# GEO-HEX-1_0_0.net
KiCad netlist of a schematic drawn in EAGLE
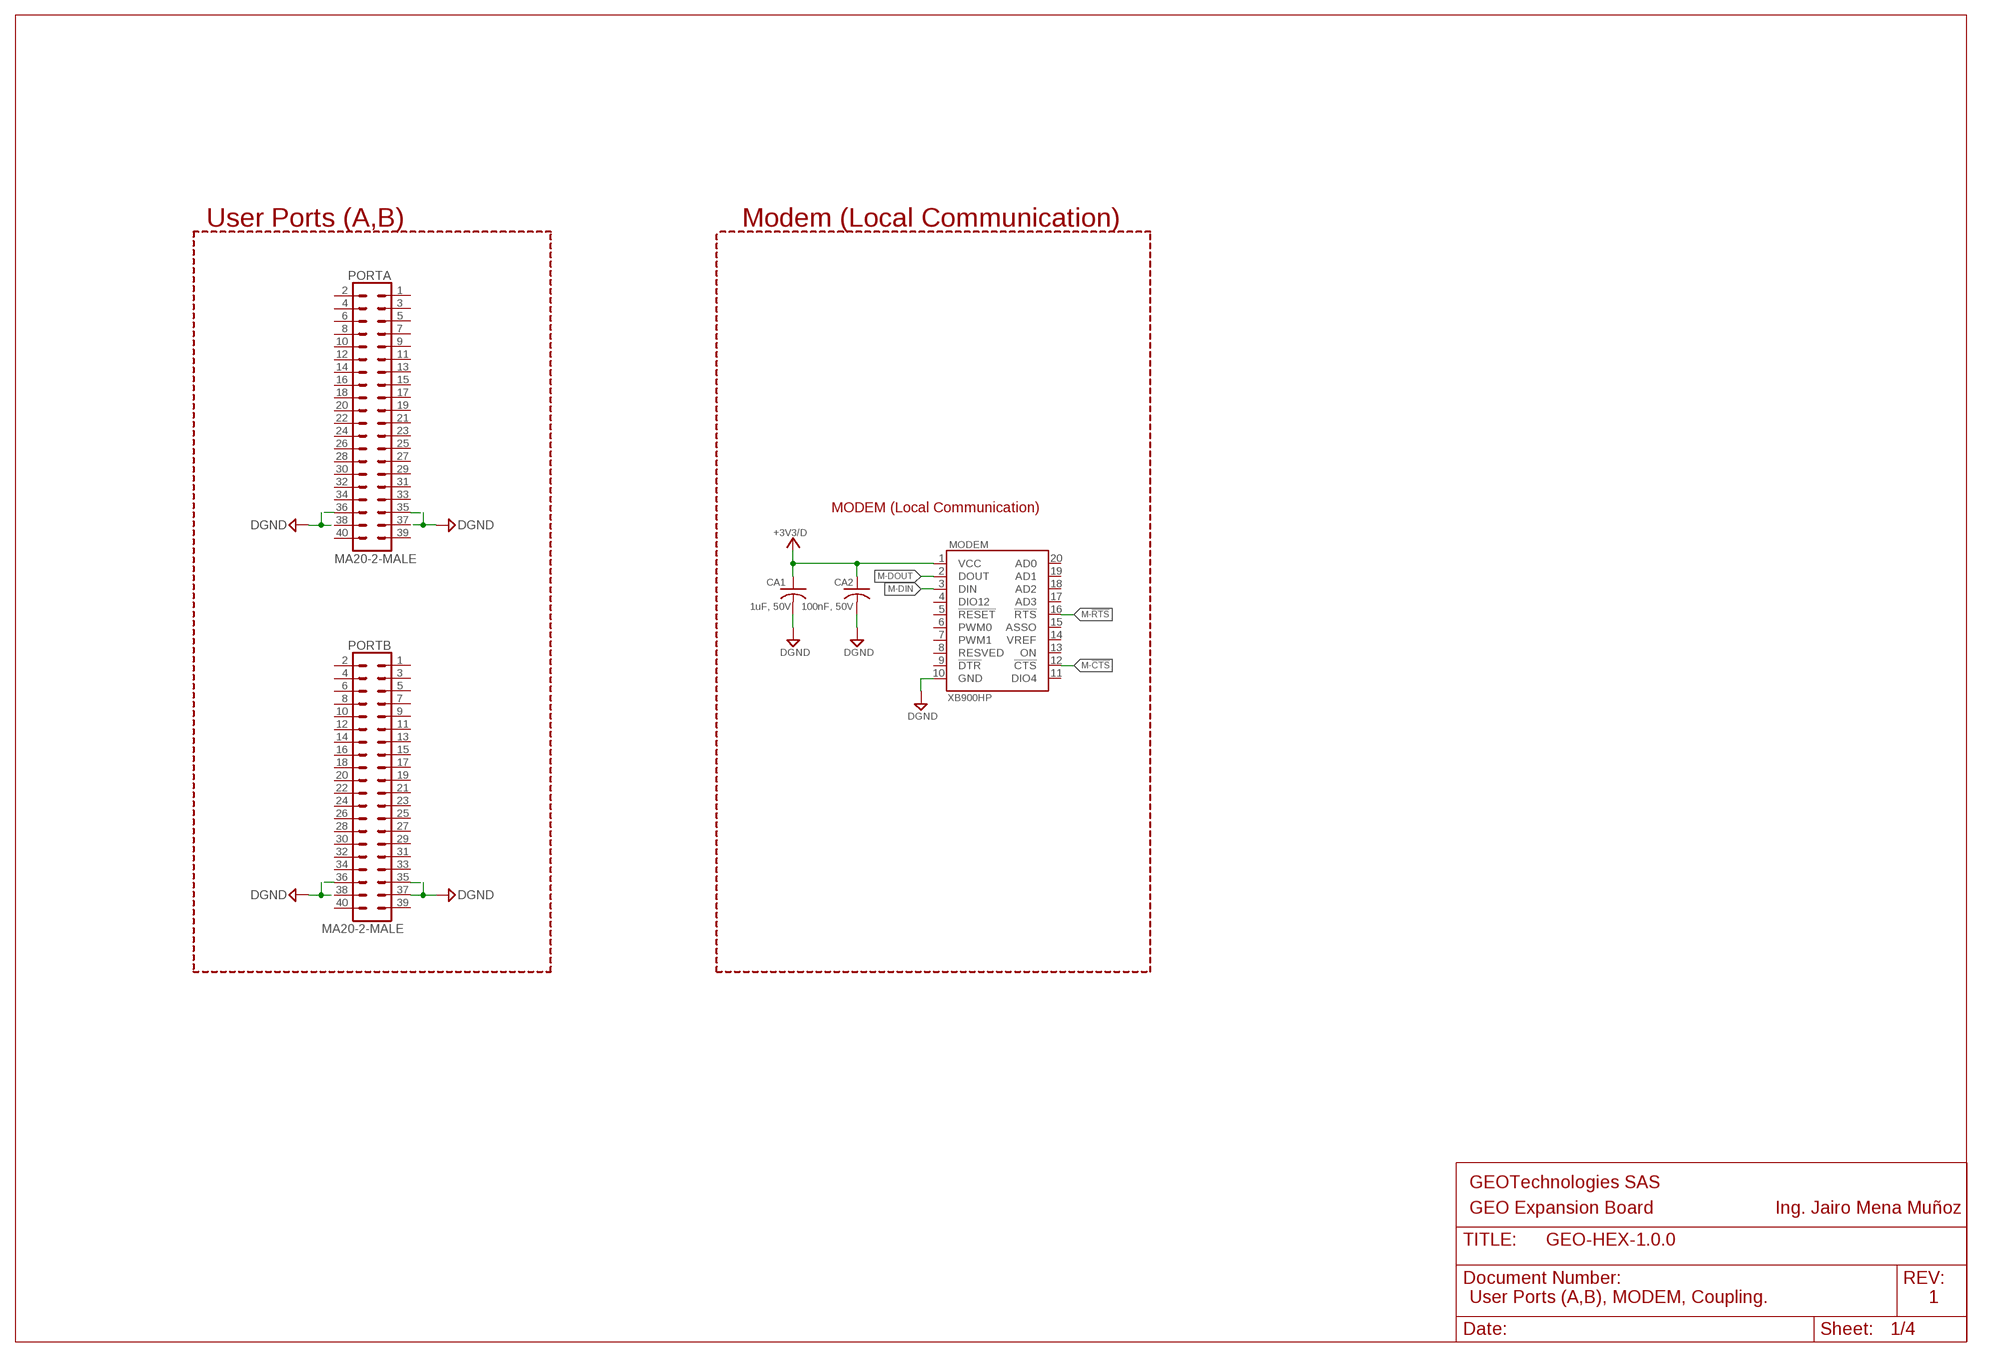
[diagram p0: schematic, sheet 1]
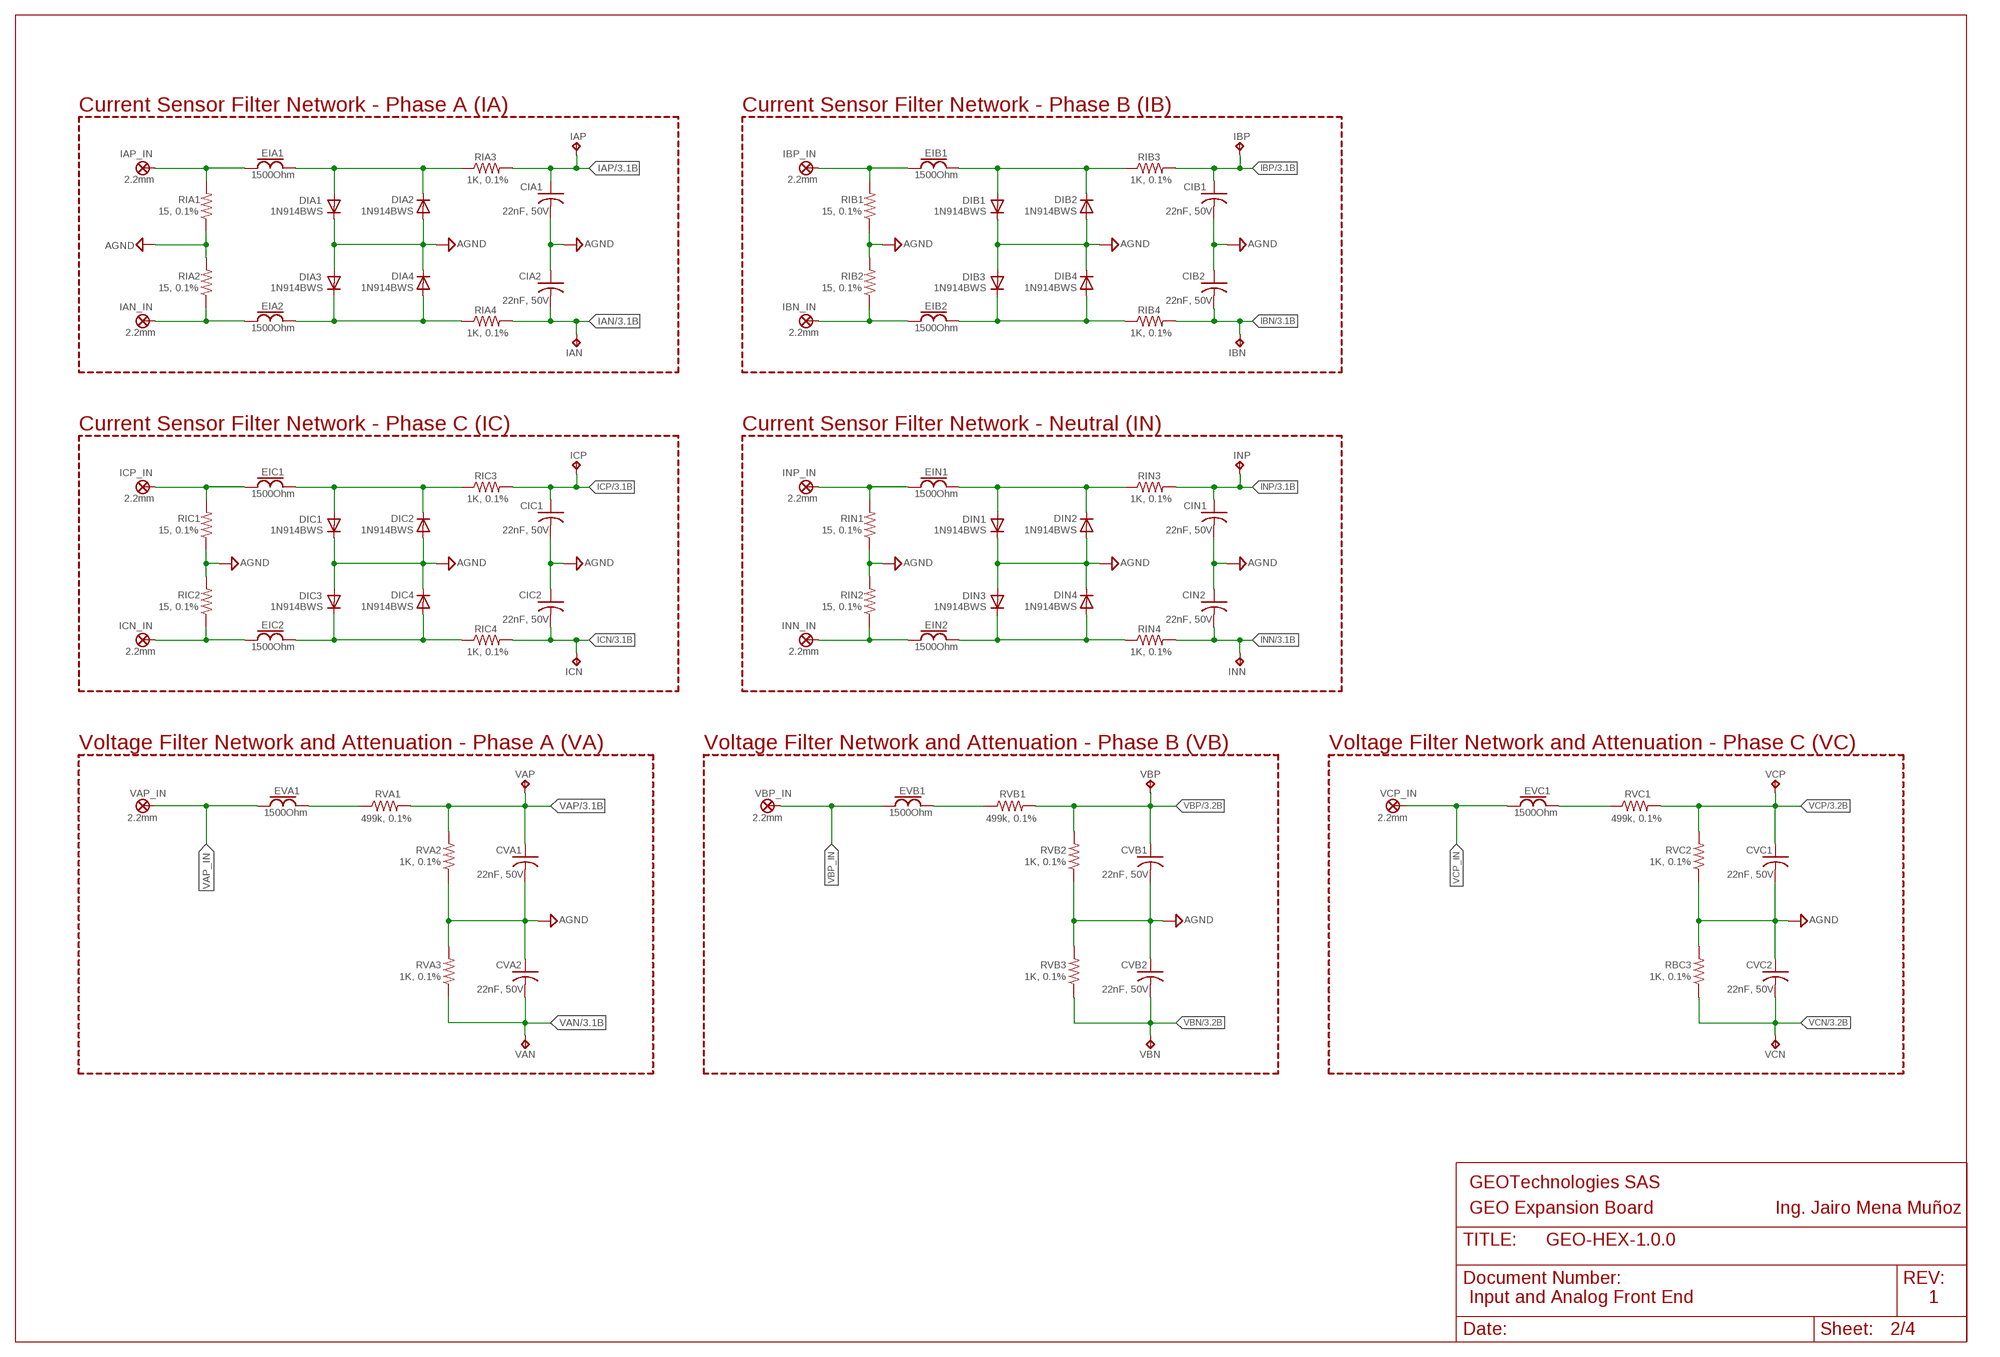
[diagram p1: schematic, sheet 2]
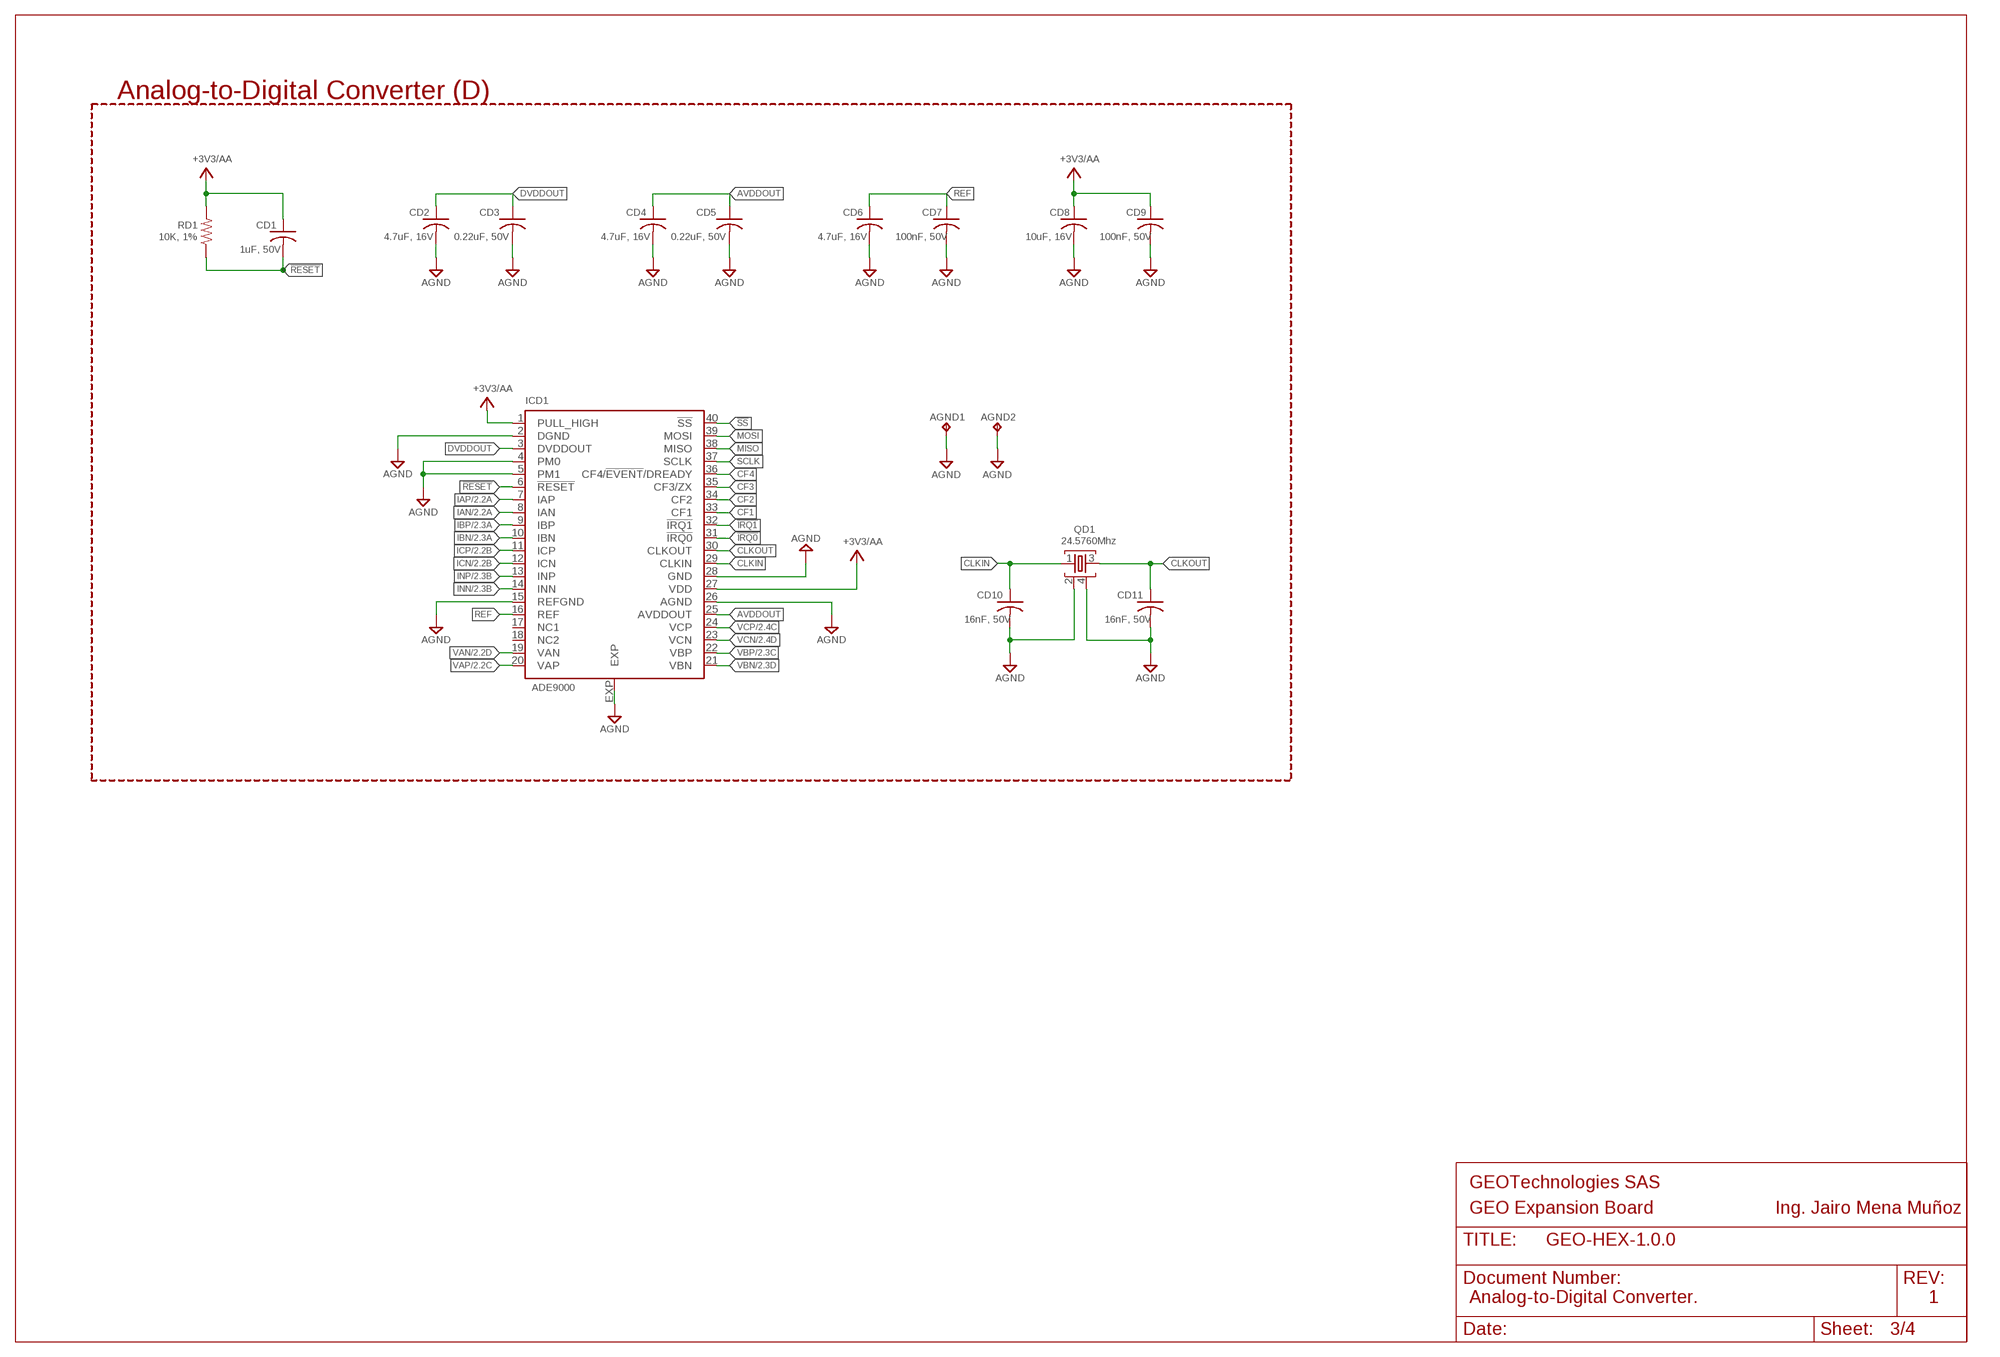
[diagram p2: schematic, sheet 3]
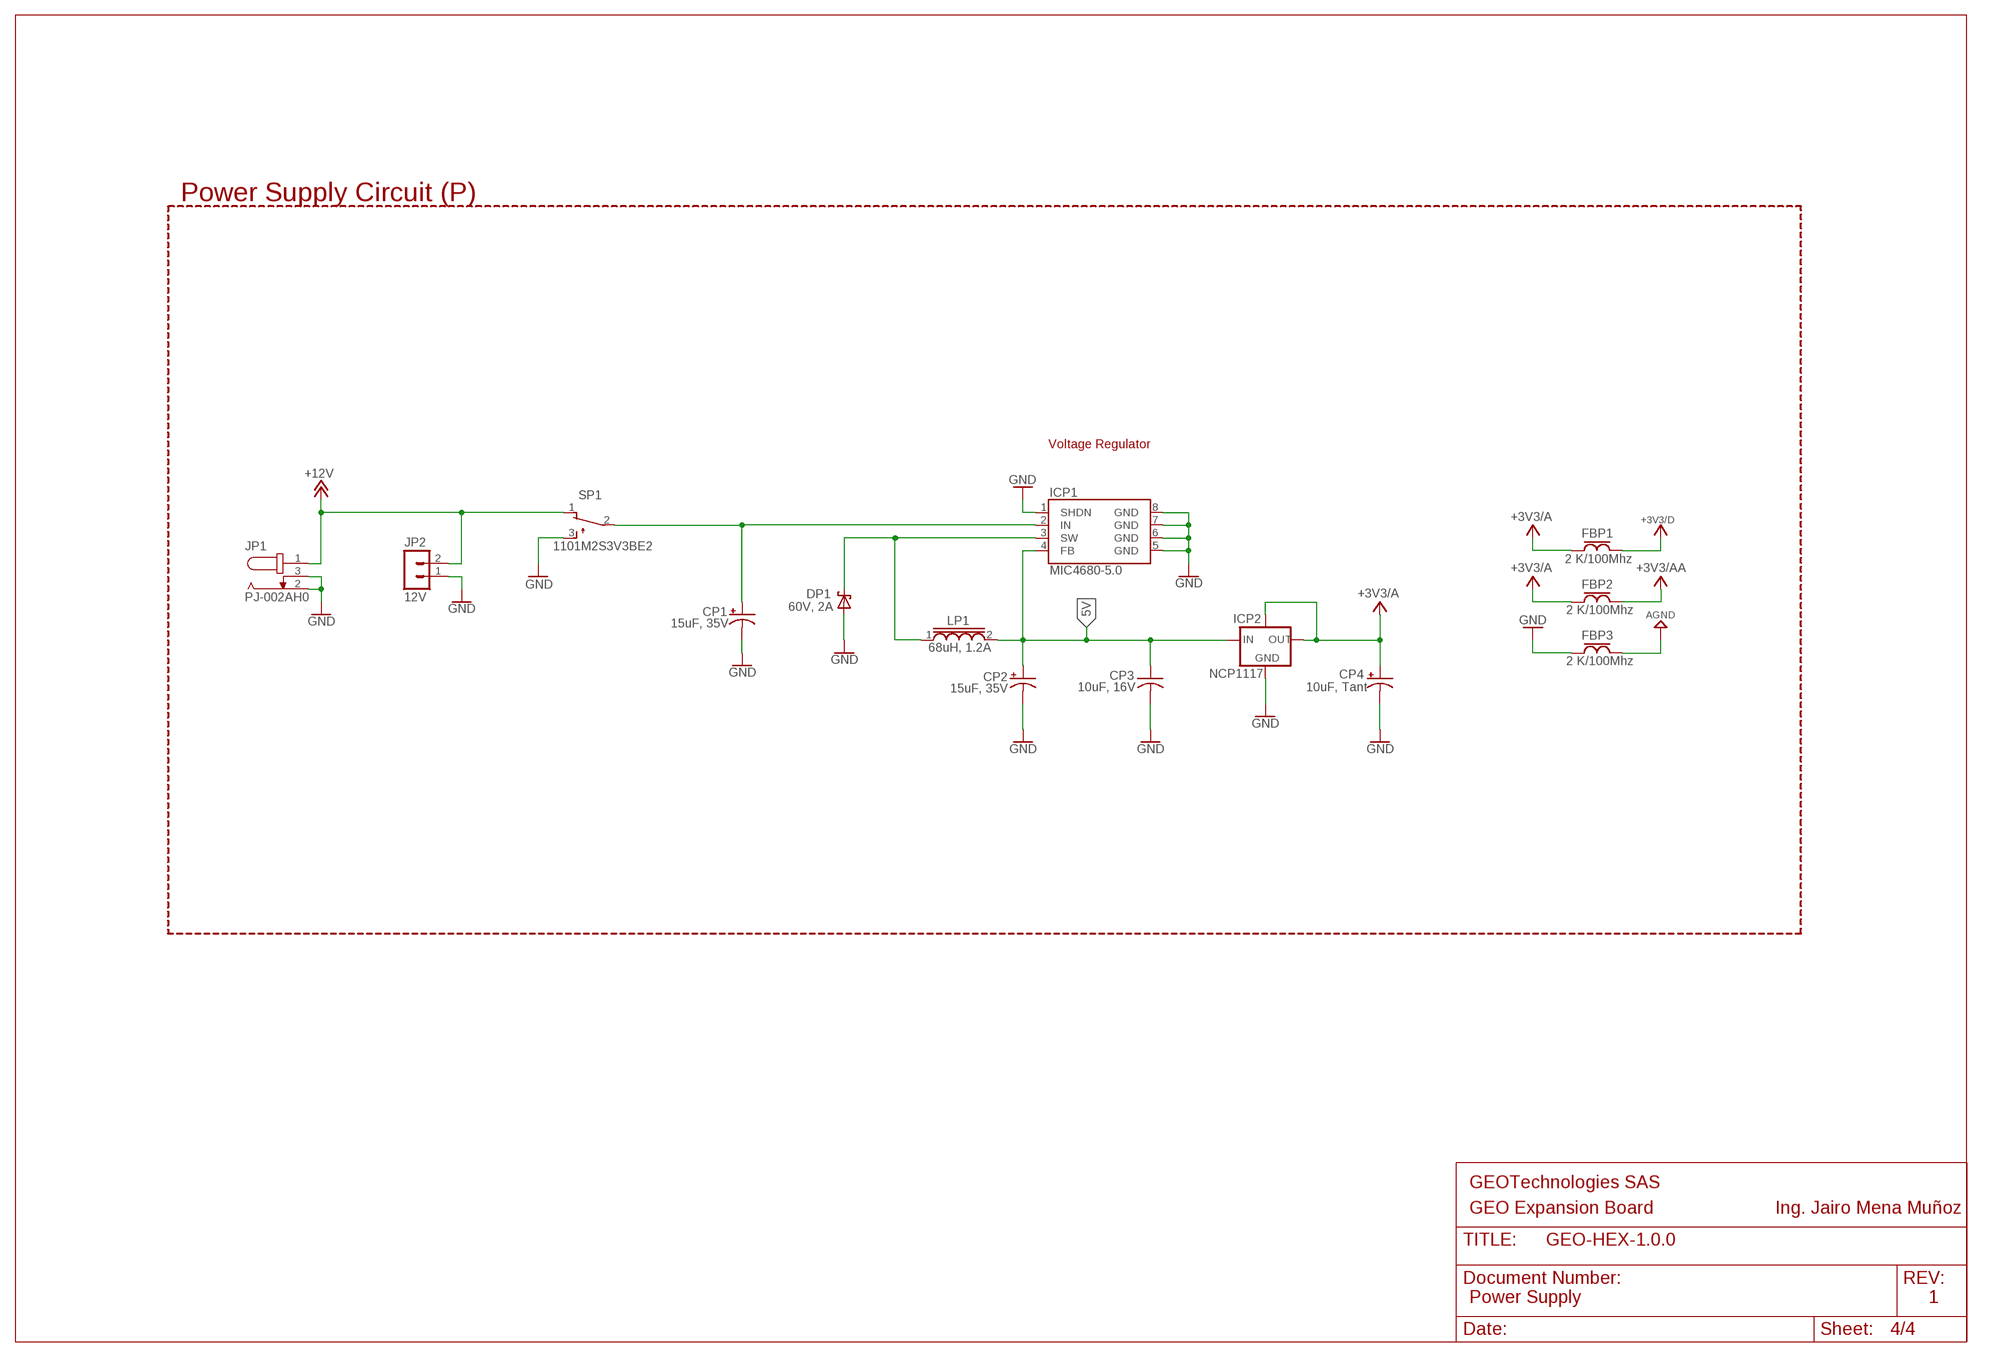
[diagram p3: schematic, sheet 4]

(export (version "E")
  (design (tool "Eeschema 10.0.6"))
  (components
    (comp (ref "CIA1")
      (value "22nF, 50V")
      (footprint "eagle-import:C0805")
      (libsource (lib "eagle-import") (part "C-US22NF-0805"))
    )
    (comp (ref "CIA2")
      (value "22nF, 50V")
      (footprint "eagle-import:C0805")
      (libsource (lib "eagle-import") (part "C-US22NF-0805"))
    )
    (comp (ref "CIB1")
      (value "22nF, 50V")
      (footprint "eagle-import:C0805")
      (libsource (lib "eagle-import") (part "C-US22NF-0805"))
    )
    (comp (ref "CIB2")
      (value "22nF, 50V")
      (footprint "eagle-import:C0805")
      (libsource (lib "eagle-import") (part "C-US22NF-0805"))
    )
    (comp (ref "CIC1")
      (value "22nF, 50V")
      (footprint "eagle-import:C0805")
      (libsource (lib "eagle-import") (part "C-US22NF-0805"))
    )
    (comp (ref "CIC2")
      (value "22nF, 50V")
      (footprint "eagle-import:C0805")
      (libsource (lib "eagle-import") (part "C-US22NF-0805"))
    )
    (comp (ref "CIN1")
      (value "22nF, 50V")
      (footprint "eagle-import:C0805")
      (libsource (lib "eagle-import") (part "C-US22NF-0805"))
    )
    (comp (ref "CIN2")
      (value "22nF, 50V")
      (footprint "eagle-import:C0805")
      (libsource (lib "eagle-import") (part "C-US22NF-0805"))
    )
    (comp (ref "CVA1")
      (value "22nF, 50V")
      (footprint "eagle-import:C0805")
      (libsource (lib "eagle-import") (part "C-US22NF-0805"))
    )
    (comp (ref "CVA2")
      (value "22nF, 50V")
      (footprint "eagle-import:C0805")
      (libsource (lib "eagle-import") (part "C-US22NF-0805"))
    )
    (comp (ref "CVB1")
      (value "22nF, 50V")
      (footprint "eagle-import:C0805")
      (libsource (lib "eagle-import") (part "C-US22NF-0805"))
    )
    (comp (ref "CVB2")
      (value "22nF, 50V")
      (footprint "eagle-import:C0805")
      (libsource (lib "eagle-import") (part "C-US22NF-0805"))
    )
    (comp (ref "CVC1")
      (value "22nF, 50V")
      (footprint "eagle-import:C0805")
      (libsource (lib "eagle-import") (part "C-US22NF-0805"))
    )
    (comp (ref "CVC2")
      (value "22nF, 50V")
      (footprint "eagle-import:C0805")
      (libsource (lib "eagle-import") (part "C-US22NF-0805"))
    )
    (comp (ref "DIA1")
      (value "1N914BWS")
      (footprint "eagle-import:SOD-323FL")
      (libsource (lib "eagle-import") (part "D1N914BWS"))
    )
    (comp (ref "DIA2")
      (value "1N914BWS")
      (footprint "eagle-import:SOD-323FL")
      (libsource (lib "eagle-import") (part "D1N914BWS"))
    )
    (comp (ref "DIA3")
      (value "1N914BWS")
      (footprint "eagle-import:SOD-323FL")
      (libsource (lib "eagle-import") (part "D1N914BWS"))
    )
    (comp (ref "DIA4")
      (value "1N914BWS")
      (footprint "eagle-import:SOD-323FL")
      (libsource (lib "eagle-import") (part "D1N914BWS"))
    )
    (comp (ref "DIB1")
      (value "1N914BWS")
      (footprint "eagle-import:SOD-323FL")
      (libsource (lib "eagle-import") (part "D1N914BWS"))
    )
    (comp (ref "DIB2")
      (value "1N914BWS")
      (footprint "eagle-import:SOD-323FL")
      (libsource (lib "eagle-import") (part "D1N914BWS"))
    )
    (comp (ref "DIB3")
      (value "1N914BWS")
      (footprint "eagle-import:SOD-323FL")
      (libsource (lib "eagle-import") (part "D1N914BWS"))
    )
    (comp (ref "DIB4")
      (value "1N914BWS")
      (footprint "eagle-import:SOD-323FL")
      (libsource (lib "eagle-import") (part "D1N914BWS"))
    )
    (comp (ref "DIC1")
      (value "1N914BWS")
      (footprint "eagle-import:SOD-323FL")
      (libsource (lib "eagle-import") (part "D1N914BWS"))
    )
    (comp (ref "DIC2")
      (value "1N914BWS")
      (footprint "eagle-import:SOD-323FL")
      (libsource (lib "eagle-import") (part "D1N914BWS"))
    )
    (comp (ref "DIC3")
      (value "1N914BWS")
      (footprint "eagle-import:SOD-323FL")
      (libsource (lib "eagle-import") (part "D1N914BWS"))
    )
    (comp (ref "DIC4")
      (value "1N914BWS")
      (footprint "eagle-import:SOD-323FL")
      (libsource (lib "eagle-import") (part "D1N914BWS"))
    )
    (comp (ref "DIN1")
      (value "1N914BWS")
      (footprint "eagle-import:SOD-323FL")
      (libsource (lib "eagle-import") (part "D1N914BWS"))
    )
    (comp (ref "DIN2")
      (value "1N914BWS")
      (footprint "eagle-import:SOD-323FL")
      (libsource (lib "eagle-import") (part "D1N914BWS"))
    )
    (comp (ref "DIN3")
      (value "1N914BWS")
      (footprint "eagle-import:SOD-323FL")
      (libsource (lib "eagle-import") (part "D1N914BWS"))
    )
    (comp (ref "DIN4")
      (value "1N914BWS")
      (footprint "eagle-import:SOD-323FL")
      (libsource (lib "eagle-import") (part "D1N914BWS"))
    )
    (comp (ref "EIA1")
      (value "1500Ohm")
      (footprint "eagle-import:L0805")
      (libsource (lib "eagle-import") (part "FBL0805"))
    )
    (comp (ref "EIA2")
      (value "1500Ohm")
      (footprint "eagle-import:L0805")
      (libsource (lib "eagle-import") (part "FBL0805"))
    )
    (comp (ref "EIB1")
      (value "1500Ohm")
      (footprint "eagle-import:L0805")
      (libsource (lib "eagle-import") (part "FBL0805"))
    )
    (comp (ref "EIB2")
      (value "1500Ohm")
      (footprint "eagle-import:L0805")
      (libsource (lib "eagle-import") (part "FBL0805"))
    )
    (comp (ref "EIC1")
      (value "1500Ohm")
      (footprint "eagle-import:L0805")
      (libsource (lib "eagle-import") (part "FBL0805"))
    )
    (comp (ref "EIC2")
      (value "1500Ohm")
      (footprint "eagle-import:L0805")
      (libsource (lib "eagle-import") (part "FBL0805"))
    )
    (comp (ref "EIN1")
      (value "1500Ohm")
      (footprint "eagle-import:L0805")
      (libsource (lib "eagle-import") (part "FBL0805"))
    )
    (comp (ref "EIN2")
      (value "1500Ohm")
      (footprint "eagle-import:L0805")
      (libsource (lib "eagle-import") (part "FBL0805"))
    )
    (comp (ref "EVA1")
      (value "1500Ohm")
      (footprint "eagle-import:L0805")
      (libsource (lib "eagle-import") (part "FBL0805"))
    )
    (comp (ref "EVB1")
      (value "1500Ohm")
      (footprint "eagle-import:L0805")
      (libsource (lib "eagle-import") (part "FBL0805"))
    )
    (comp (ref "EVC1")
      (value "1500Ohm")
      (footprint "eagle-import:L0805")
      (libsource (lib "eagle-import") (part "FBL0805"))
    )
    (comp (ref "IAN")
      (value "TPPAD1-13")
      (footprint "eagle-import:P1-10")
      (libsource (lib "eagle-import") (part "TPPAD1-13"))
    )
    (comp (ref "IAN_IN")
      (value "2.2mm")
      (footprint "eagle-import:TURRET")
      (libsource (lib "eagle-import") (part "TURRET"))
    )
    (comp (ref "IAP")
      (value "TPPAD1-13")
      (footprint "eagle-import:P1-10")
      (libsource (lib "eagle-import") (part "TPPAD1-13"))
    )
    (comp (ref "IAP_IN")
      (value "2.2mm")
      (footprint "eagle-import:TURRET")
      (libsource (lib "eagle-import") (part "TURRET"))
    )
    (comp (ref "IBN")
      (value "TPPAD1-13")
      (footprint "eagle-import:P1-10")
      (libsource (lib "eagle-import") (part "TPPAD1-13"))
    )
    (comp (ref "IBN_IN")
      (value "2.2mm")
      (footprint "eagle-import:TURRET")
      (libsource (lib "eagle-import") (part "TURRET"))
    )
    (comp (ref "IBP")
      (value "TPPAD1-13")
      (footprint "eagle-import:P1-10")
      (libsource (lib "eagle-import") (part "TPPAD1-13"))
    )
    (comp (ref "IBP_IN")
      (value "2.2mm")
      (footprint "eagle-import:TURRET")
      (libsource (lib "eagle-import") (part "TURRET"))
    )
    (comp (ref "ICN")
      (value "TPPAD1-13")
      (footprint "eagle-import:P1-10")
      (libsource (lib "eagle-import") (part "TPPAD1-13"))
    )
    (comp (ref "ICN_IN")
      (value "2.2mm")
      (footprint "eagle-import:TURRET")
      (libsource (lib "eagle-import") (part "TURRET"))
    )
    (comp (ref "ICP")
      (value "TPPAD1-13")
      (footprint "eagle-import:P1-10")
      (libsource (lib "eagle-import") (part "TPPAD1-13"))
    )
    (comp (ref "ICP_IN")
      (value "2.2mm")
      (footprint "eagle-import:TURRET")
      (libsource (lib "eagle-import") (part "TURRET"))
    )
    (comp (ref "INN")
      (value "TPPAD1-13")
      (footprint "eagle-import:P1-10")
      (libsource (lib "eagle-import") (part "TPPAD1-13"))
    )
    (comp (ref "INN_IN")
      (value "2.2mm")
      (footprint "eagle-import:TURRET")
      (libsource (lib "eagle-import") (part "TURRET"))
    )
    (comp (ref "INP")
      (value "TPPAD1-13")
      (footprint "eagle-import:P1-10")
      (libsource (lib "eagle-import") (part "TPPAD1-13"))
    )
    (comp (ref "INP_IN")
      (value "2.2mm")
      (footprint "eagle-import:TURRET")
      (libsource (lib "eagle-import") (part "TURRET"))
    )
    (comp (ref "RBC3")
      (value "1K, 0.1%")
      (footprint "eagle-import:R0805")
      (libsource (lib "eagle-import") (part "R-US1KR0805"))
    )
    (comp (ref "RIA1")
      (value "15, 0.1%")
      (footprint "eagle-import:R0805")
      (libsource (lib "eagle-import") (part "R-US15R0805"))
    )
    (comp (ref "RIA2")
      (value "15, 0.1%")
      (footprint "eagle-import:R0805")
      (libsource (lib "eagle-import") (part "R-US15R0805"))
    )
    (comp (ref "RIA3")
      (value "1K, 0.1%")
      (footprint "eagle-import:R0805")
      (libsource (lib "eagle-import") (part "R-US1KR0805"))
    )
    (comp (ref "RIA4")
      (value "1K, 0.1%")
      (footprint "eagle-import:R0805")
      (libsource (lib "eagle-import") (part "R-US1KR0805"))
    )
    (comp (ref "RIB1")
      (value "15, 0.1%")
      (footprint "eagle-import:R0805")
      (libsource (lib "eagle-import") (part "R-US15R0805"))
    )
    (comp (ref "RIB2")
      (value "15, 0.1%")
      (footprint "eagle-import:R0805")
      (libsource (lib "eagle-import") (part "R-US15R0805"))
    )
    (comp (ref "RIB3")
      (value "1K, 0.1%")
      (footprint "eagle-import:R0805")
      (libsource (lib "eagle-import") (part "R-US1KR0805"))
    )
    (comp (ref "RIB4")
      (value "1K, 0.1%")
      (footprint "eagle-import:R0805")
      (libsource (lib "eagle-import") (part "R-US1KR0805"))
    )
    (comp (ref "RIC1")
      (value "15, 0.1%")
      (footprint "eagle-import:R0805")
      (libsource (lib "eagle-import") (part "R-US15R0805"))
    )
    (comp (ref "RIC2")
      (value "15, 0.1%")
      (footprint "eagle-import:R0805")
      (libsource (lib "eagle-import") (part "R-US15R0805"))
    )
    (comp (ref "RIC3")
      (value "1K, 0.1%")
      (footprint "eagle-import:R0805")
      (libsource (lib "eagle-import") (part "R-US1KR0805"))
    )
    (comp (ref "RIC4")
      (value "1K, 0.1%")
      (footprint "eagle-import:R0805")
      (libsource (lib "eagle-import") (part "R-US1KR0805"))
    )
    (comp (ref "RIN1")
      (value "15, 0.1%")
      (footprint "eagle-import:R0805")
      (libsource (lib "eagle-import") (part "R-US15R0805"))
    )
    (comp (ref "RIN2")
      (value "15, 0.1%")
      (footprint "eagle-import:R0805")
      (libsource (lib "eagle-import") (part "R-US15R0805"))
    )
    (comp (ref "RIN3")
      (value "1K, 0.1%")
      (footprint "eagle-import:R0805")
      (libsource (lib "eagle-import") (part "R-US1KR0805"))
    )
    (comp (ref "RIN4")
      (value "1K, 0.1%")
      (footprint "eagle-import:R0805")
      (libsource (lib "eagle-import") (part "R-US1KR0805"))
    )
    (comp (ref "RVA1")
      (value "499k, 0.1%")
      (footprint "eagle-import:R1206")
      (libsource (lib "eagle-import") (part "R-US499KR1206"))
    )
    (comp (ref "RVA2")
      (value "1K, 0.1%")
      (footprint "eagle-import:R0805")
      (libsource (lib "eagle-import") (part "R-US1KR0805"))
    )
    (comp (ref "RVA3")
      (value "1K, 0.1%")
      (footprint "eagle-import:R0805")
      (libsource (lib "eagle-import") (part "R-US1KR0805"))
    )
    (comp (ref "RVB1")
      (value "499k, 0.1%")
      (footprint "eagle-import:R1206")
      (libsource (lib "eagle-import") (part "R-US499KR1206"))
    )
    (comp (ref "RVB2")
      (value "1K, 0.1%")
      (footprint "eagle-import:R0805")
      (libsource (lib "eagle-import") (part "R-US1KR0805"))
    )
    (comp (ref "RVB3")
      (value "1K, 0.1%")
      (footprint "eagle-import:R0805")
      (libsource (lib "eagle-import") (part "R-US1KR0805"))
    )
    (comp (ref "RVC1")
      (value "499k, 0.1%")
      (footprint "eagle-import:R1206")
      (libsource (lib "eagle-import") (part "R-US499KR1206"))
    )
    (comp (ref "RVC2")
      (value "1K, 0.1%")
      (footprint "eagle-import:R0805")
      (libsource (lib "eagle-import") (part "R-US1KR0805"))
    )
    (comp (ref "VAN")
      (value "TPPAD1-13")
      (footprint "eagle-import:P1-10")
      (libsource (lib "eagle-import") (part "TPPAD1-13"))
    )
    (comp (ref "VAP")
      (value "TPPAD1-13")
      (footprint "eagle-import:P1-10")
      (libsource (lib "eagle-import") (part "TPPAD1-13"))
    )
    (comp (ref "VAP_IN")
      (value "2.2mm")
      (footprint "eagle-import:TURRET")
      (libsource (lib "eagle-import") (part "TURRET"))
    )
    (comp (ref "VBN")
      (value "TPPAD1-13")
      (footprint "eagle-import:P1-10")
      (libsource (lib "eagle-import") (part "TPPAD1-13"))
    )
    (comp (ref "VBP")
      (value "TPPAD1-13")
      (footprint "eagle-import:P1-10")
      (libsource (lib "eagle-import") (part "TPPAD1-13"))
    )
    (comp (ref "VBP_IN")
      (value "2.2mm")
      (footprint "eagle-import:TURRET")
      (libsource (lib "eagle-import") (part "TURRET"))
    )
    (comp (ref "VCN")
      (value "TPPAD1-13")
      (footprint "eagle-import:P1-10")
      (libsource (lib "eagle-import") (part "TPPAD1-13"))
    )
    (comp (ref "VCP")
      (value "TPPAD1-13")
      (footprint "eagle-import:P1-10")
      (libsource (lib "eagle-import") (part "TPPAD1-13"))
    )
    (comp (ref "VCP_IN")
      (value "2.2mm")
      (footprint "eagle-import:TURRET")
      (libsource (lib "eagle-import") (part "TURRET"))
    )
    (comp (ref "CA1")
      (value "1uF, 50V")
      (footprint "eagle-import:C0805")
      (libsource (lib "eagle-import") (part "C-US1UF-0805"))
    )
    (comp (ref "CA2")
      (value "100nF, 50V")
      (footprint "eagle-import:C0805")
      (libsource (lib "eagle-import") (part "C-US100NF-0805"))
    )
    (comp (ref "MODEM")
      (value "XB900HP")
      (footprint "eagle-import:XBEEPRO")
      (libsource (lib "eagle-import") (part "XBEEPROXBP9B-DMST-002"))
    )
    (comp (ref "PORTA")
      (value "MA20-2-MALE")
      (footprint "eagle-import:MA20-2-MALE")
      (libsource (lib "eagle-import") (part "MA20-2-MALE"))
    )
    (comp (ref "PORTB")
      (value "MA20-2-MALE")
      (footprint "eagle-import:MA20-2-MALE")
      (libsource (lib "eagle-import") (part "MA20-2-MALE"))
    )
    (comp (ref "CP1")
      (value "15uF, 35V")
      (footprint "eagle-import:SMC_D")
      (libsource (lib "eagle-import") (part "C-POLSMCD"))
    )
    (comp (ref "CP2")
      (value "15uF, 35V")
      (footprint "eagle-import:SMC_D")
      (libsource (lib "eagle-import") (part "C-POLSMCD"))
    )
    (comp (ref "CP3")
      (value "10uF, 16V")
      (footprint "eagle-import:C0805")
      (libsource (lib "eagle-import") (part "C-US10UF-0805"))
    )
    (comp (ref "CP4")
      (value "10uF, Tant")
      (footprint "eagle-import:SMC_P")
      (libsource (lib "eagle-import") (part "C-POLSMCP"))
    )
    (comp (ref "DP1")
      (value "60V, 2A")
      (footprint "eagle-import:2-SMD")
      (libsource (lib "eagle-import") (part "DSB260A"))
    )
    (comp (ref "FBP1")
      (value "2 K/100Mhz")
      (footprint "eagle-import:L1210")
      (libsource (lib "eagle-import") (part "FBL1210"))
    )
    (comp (ref "FBP2")
      (value "2 K/100Mhz")
      (footprint "eagle-import:L1210")
      (libsource (lib "eagle-import") (part "FBL1210"))
    )
    (comp (ref "FBP3")
      (value "2 K/100Mhz")
      (footprint "eagle-import:L1210")
      (libsource (lib "eagle-import") (part "FBL1210"))
    )
    (comp (ref "ICP1")
      (value "MIC4680-5.0")
      (footprint "eagle-import:SO8")
      (libsource (lib "eagle-import") (part "MIC4680"))
    )
    (comp (ref "ICP2")
      (value "NCP1117")
      (footprint "eagle-import:SOT223")
      (libsource (lib "eagle-import") (part "NCP1117"))
    )
    (comp (ref "JP1")
      (value "PJ-002AH0")
      (footprint "eagle-import:JACK")
      (libsource (lib "eagle-import") (part "PJ-002AH0"))
    )
    (comp (ref "JP2")
      (value "12V")
      (footprint "eagle-import:PW2")
      (libsource (lib "eagle-import") (part "PW2"))
    )
    (comp (ref "LP1")
      (value "68uH, 1.2A")
      (footprint "eagle-import:DR7X7")
      (libsource (lib "eagle-import") (part "LVLP8040T-680M"))
    )
    (comp (ref "SP1")
      (value "1101M2S3V3BE2")
      (footprint "eagle-import:1101M2S3V3BE2")
      (libsource (lib "eagle-import") (part "1101M2S3V3BE2"))
    )
    (comp (ref "AGND1")
      (value "TPPAD1-13")
      (footprint "eagle-import:P1-10")
      (libsource (lib "eagle-import") (part "TPPAD1-13"))
    )
    (comp (ref "AGND2")
      (value "TPPAD1-13")
      (footprint "eagle-import:P1-10")
      (libsource (lib "eagle-import") (part "TPPAD1-13"))
    )
    (comp (ref "CD1")
      (value "1uF, 50V")
      (footprint "eagle-import:C0805")
      (libsource (lib "eagle-import") (part "C-US1UF-0805"))
    )
    (comp (ref "CD2")
      (value "4.7uF, 16V")
      (footprint "eagle-import:C0805")
      (libsource (lib "eagle-import") (part "C-US4.7UF-0805"))
    )
    (comp (ref "CD3")
      (value "0.22uF, 50V")
      (footprint "eagle-import:C0805")
      (libsource (lib "eagle-import") (part "C-US0.22UF-0805"))
    )
    (comp (ref "CD4")
      (value "4.7uF, 16V")
      (footprint "eagle-import:C0805")
      (libsource (lib "eagle-import") (part "C-US4.7UF-0805"))
    )
    (comp (ref "CD5")
      (value "0.22uF, 50V")
      (footprint "eagle-import:C0805")
      (libsource (lib "eagle-import") (part "C-US0.22UF-0805"))
    )
    (comp (ref "CD6")
      (value "4.7uF, 16V")
      (footprint "eagle-import:C0805")
      (libsource (lib "eagle-import") (part "C-US4.7UF-0805"))
    )
    (comp (ref "CD7")
      (value "100nF, 50V")
      (footprint "eagle-import:C0805")
      (libsource (lib "eagle-import") (part "C-US100NF-0805"))
    )
    (comp (ref "CD8")
      (value "10uF, 16V")
      (footprint "eagle-import:C0805")
      (libsource (lib "eagle-import") (part "C-US10UF-0805"))
    )
    (comp (ref "CD9")
      (value "100nF, 50V")
      (footprint "eagle-import:C0805")
      (libsource (lib "eagle-import") (part "C-US100NF-0805"))
    )
    (comp (ref "CD10")
      (value "16nF, 50V")
      (footprint "eagle-import:C0805")
      (libsource (lib "eagle-import") (part "C-US16PF-0805"))
    )
    (comp (ref "CD11")
      (value "16nF, 50V")
      (footprint "eagle-import:C0805")
      (libsource (lib "eagle-import") (part "C-US16PF-0805"))
    )
    (comp (ref "ICD1")
      (value "ADE9000")
      (footprint "eagle-import:LFCSP40")
      (libsource (lib "eagle-import") (part "ADE9000"))
    )
    (comp (ref "QD1")
      (value "24.5760Mhz")
      (footprint "eagle-import:4-SMD")
      (libsource (lib "eagle-import") (part "Q-SHIELD"))
    )
    (comp (ref "RD1")
      (value "10K, 1%")
      (footprint "eagle-import:R0805")
      (libsource (lib "eagle-import") (part "R-US10KR0805"))
    )
  )
  (nets
    (net (code "1") (name "+3V3{slash}A") (class "Default")
      (node (ref "CP4") (pin "+") (pinfunction "+_+") (pintype "passive"))
      (node (ref "FBP1") (pin "1") (pinfunction "P$1_1") (pintype "passive"))
      (node (ref "FBP2") (pin "1") (pinfunction "P$1_1") (pintype "passive"))
      (node (ref "ICP2") (pin "2") (pinfunction "OUT_2") (pintype "power_in"))
      (node (ref "ICP2") (pin "4") (pinfunction "TAB_4") (pintype "power_in"))
    )
    (net (code "2") (name "+3V3{slash}AA") (class "Default")
      (node (ref "CD1") (pin "1") (pinfunction "1_1") (pintype "passive"))
      (node (ref "CD8") (pin "1") (pinfunction "1_1") (pintype "passive"))
      (node (ref "CD9") (pin "1") (pinfunction "1_1") (pintype "passive"))
      (node (ref "FBP2") (pin "2") (pinfunction "P$2_2") (pintype "passive"))
      (node (ref "ICD1") (pin "1") (pinfunction "PULL_HIGH_1") (pintype "bidirectional"))
      (node (ref "ICD1") (pin "27") (pinfunction "VDD_27") (pintype "power_in"))
      (node (ref "RD1") (pin "2") (pinfunction "2_2") (pintype "passive"))
    )
    (net (code "3") (name "+3V3{slash}D") (class "Default")
      (node (ref "CA1") (pin "1") (pinfunction "1_1") (pintype "passive"))
      (node (ref "CA2") (pin "1") (pinfunction "1_1") (pintype "passive"))
      (node (ref "FBP1") (pin "2") (pinfunction "P$2_2") (pintype "passive"))
      (node (ref "MODEM") (pin "1") (pinfunction "VCC_1") (pintype "power_in"))
    )
    (net (code "4") (name "+12V") (class "Default")
      (node (ref "JP1") (pin "1") (pinfunction "1_1") (pintype "passive"))
      (node (ref "JP2") (pin "2") (pinfunction "2_2") (pintype "passive"))
      (node (ref "SP1") (pin "1") (pinfunction "1_1") (pintype "passive"))
    )
    (net (code "5") (name "5V") (class "Default")
      (node (ref "CP2") (pin "+") (pinfunction "+_+") (pintype "passive"))
      (node (ref "CP3") (pin "1") (pinfunction "1_1") (pintype "passive"))
      (node (ref "ICP1") (pin "4") (pinfunction "FB_4") (pintype "bidirectional"))
      (node (ref "ICP2") (pin "3") (pinfunction "IN_3") (pintype "input"))
      (node (ref "LP1") (pin "2") (pinfunction "2_2") (pintype "passive"))
    )
    (net (code "6") (name "AGND") (class "Default")
      (node (ref "AGND1") (pin "TP") (pinfunction "TP_TP") (pintype "input"))
      (node (ref "AGND2") (pin "TP") (pinfunction "TP_TP") (pintype "input"))
      (node (ref "CD10") (pin "2") (pinfunction "2_2") (pintype "passive"))
      (node (ref "CD11") (pin "2") (pinfunction "2_2") (pintype "passive"))
      (node (ref "CD2") (pin "2") (pinfunction "2_2") (pintype "passive"))
      (node (ref "CD3") (pin "2") (pinfunction "2_2") (pintype "passive"))
      (node (ref "CD4") (pin "2") (pinfunction "2_2") (pintype "passive"))
      (node (ref "CD5") (pin "2") (pinfunction "2_2") (pintype "passive"))
      (node (ref "CD6") (pin "2") (pinfunction "2_2") (pintype "passive"))
      (node (ref "CD7") (pin "2") (pinfunction "2_2") (pintype "passive"))
      (node (ref "CD8") (pin "2") (pinfunction "2_2") (pintype "passive"))
      (node (ref "CD9") (pin "2") (pinfunction "2_2") (pintype "passive"))
      (node (ref "CIA1") (pin "2") (pinfunction "2_2") (pintype "passive"))
      (node (ref "CIA2") (pin "1") (pinfunction "1_1") (pintype "passive"))
      (node (ref "CIB1") (pin "2") (pinfunction "2_2") (pintype "passive"))
      (node (ref "CIB2") (pin "1") (pinfunction "1_1") (pintype "passive"))
      (node (ref "CIC1") (pin "2") (pinfunction "2_2") (pintype "passive"))
      (node (ref "CIC2") (pin "1") (pinfunction "1_1") (pintype "passive"))
      (node (ref "CIN1") (pin "2") (pinfunction "2_2") (pintype "passive"))
      (node (ref "CIN2") (pin "1") (pinfunction "1_1") (pintype "passive"))
      (node (ref "CVA1") (pin "2") (pinfunction "2_2") (pintype "passive"))
      (node (ref "CVA2") (pin "1") (pinfunction "1_1") (pintype "passive"))
      (node (ref "CVB1") (pin "2") (pinfunction "2_2") (pintype "passive"))
      (node (ref "CVB2") (pin "1") (pinfunction "1_1") (pintype "passive"))
      (node (ref "CVC1") (pin "2") (pinfunction "2_2") (pintype "passive"))
      (node (ref "CVC2") (pin "1") (pinfunction "1_1") (pintype "passive"))
      (node (ref "DIA1") (pin "C") (pinfunction "C_C") (pintype "passive"))
      (node (ref "DIA2") (pin "A") (pinfunction "A_A") (pintype "passive"))
      (node (ref "DIA3") (pin "A") (pinfunction "A_A") (pintype "passive"))
      (node (ref "DIA4") (pin "C") (pinfunction "C_C") (pintype "passive"))
      (node (ref "DIB1") (pin "C") (pinfunction "C_C") (pintype "passive"))
      (node (ref "DIB2") (pin "A") (pinfunction "A_A") (pintype "passive"))
      (node (ref "DIB3") (pin "A") (pinfunction "A_A") (pintype "passive"))
      (node (ref "DIB4") (pin "C") (pinfunction "C_C") (pintype "passive"))
      (node (ref "DIC1") (pin "C") (pinfunction "C_C") (pintype "passive"))
      (node (ref "DIC2") (pin "A") (pinfunction "A_A") (pintype "passive"))
      (node (ref "DIC3") (pin "A") (pinfunction "A_A") (pintype "passive"))
      (node (ref "DIC4") (pin "C") (pinfunction "C_C") (pintype "passive"))
      (node (ref "DIN1") (pin "C") (pinfunction "C_C") (pintype "passive"))
      (node (ref "DIN2") (pin "A") (pinfunction "A_A") (pintype "passive"))
      (node (ref "DIN3") (pin "A") (pinfunction "A_A") (pintype "passive"))
      (node (ref "DIN4") (pin "C") (pinfunction "C_C") (pintype "passive"))
      (node (ref "FBP3") (pin "2") (pinfunction "P$2_2") (pintype "passive"))
      (node (ref "ICD1") (pin "15") (pinfunction "REFGND_15") (pintype "passive"))
      (node (ref "ICD1") (pin "2") (pinfunction "DGND_2") (pintype "power_in"))
      (node (ref "ICD1") (pin "26") (pinfunction "AGND_26") (pintype "power_in"))
      (node (ref "ICD1") (pin "28") (pinfunction "GND_28") (pintype "power_in"))
      (node (ref "ICD1") (pin "4") (pinfunction "PM0_4") (pintype "input"))
      (node (ref "ICD1") (pin "5") (pinfunction "PM1_5") (pintype "input"))
      (node (ref "ICD1") (pin "EXP") (pinfunction "EXP_EXP") (pintype "passive"))
      (node (ref "QD1") (pin "2") (pinfunction "2_2") (pintype "passive"))
      (node (ref "QD1") (pin "4") (pinfunction "4_4") (pintype "passive"))
      (node (ref "RBC3") (pin "2") (pinfunction "2_2") (pintype "passive"))
      (node (ref "RIA1") (pin "1") (pinfunction "1_1") (pintype "passive"))
      (node (ref "RIA2") (pin "2") (pinfunction "2_2") (pintype "passive"))
      (node (ref "RIB1") (pin "1") (pinfunction "1_1") (pintype "passive"))
      (node (ref "RIB2") (pin "2") (pinfunction "2_2") (pintype "passive"))
      (node (ref "RIC1") (pin "1") (pinfunction "1_1") (pintype "passive"))
      (node (ref "RIC2") (pin "2") (pinfunction "2_2") (pintype "passive"))
      (node (ref "RIN1") (pin "1") (pinfunction "1_1") (pintype "passive"))
      (node (ref "RIN2") (pin "2") (pinfunction "2_2") (pintype "passive"))
      (node (ref "RVA2") (pin "1") (pinfunction "1_1") (pintype "passive"))
      (node (ref "RVA3") (pin "2") (pinfunction "2_2") (pintype "passive"))
      (node (ref "RVB2") (pin "1") (pinfunction "1_1") (pintype "passive"))
      (node (ref "RVB3") (pin "2") (pinfunction "2_2") (pintype "passive"))
      (node (ref "RVC2") (pin "1") (pinfunction "1_1") (pintype "passive"))
    )
    (net (code "7") (name "AVDDOUT") (class "Default")
      (node (ref "CD4") (pin "1") (pinfunction "1_1") (pintype "passive"))
      (node (ref "CD5") (pin "1") (pinfunction "1_1") (pintype "passive"))
      (node (ref "ICD1") (pin "25") (pinfunction "AVDDOUT_25") (pintype "output"))
    )
    (net (code "8") (name "CF1") (class "Default")
      (node (ref "ICD1") (pin "33") (pinfunction "CF1_33") (pintype "output"))
    )
    (net (code "9") (name "CF2") (class "Default")
      (node (ref "ICD1") (pin "34") (pinfunction "CF2_34") (pintype "output"))
    )
    (net (code "10") (name "CF3") (class "Default")
      (node (ref "ICD1") (pin "35") (pinfunction "CF3/ZX_35") (pintype "output"))
    )
    (net (code "11") (name "CF4") (class "Default")
      (node (ref "ICD1") (pin "36") (pinfunction "CF4/~{EVENT}/DREADY_36") (pintype "output"))
    )
    (net (code "12") (name "CLKIN") (class "Default")
      (node (ref "CD10") (pin "1") (pinfunction "1_1") (pintype "passive"))
      (node (ref "ICD1") (pin "29") (pinfunction "CLKIN_29") (pintype "passive"))
      (node (ref "QD1") (pin "1") (pinfunction "1_1") (pintype "passive"))
    )
    (net (code "13") (name "CLKOUT") (class "Default")
      (node (ref "CD11") (pin "1") (pinfunction "1_1") (pintype "passive"))
      (node (ref "ICD1") (pin "30") (pinfunction "CLKOUT_30") (pintype "passive"))
      (node (ref "QD1") (pin "3") (pinfunction "3_3") (pintype "passive"))
    )
    (net (code "14") (name "DGND") (class "Default")
      (node (ref "CA1") (pin "2") (pinfunction "2_2") (pintype "passive"))
      (node (ref "CA2") (pin "2") (pinfunction "2_2") (pintype "passive"))
      (node (ref "MODEM") (pin "10") (pinfunction "GND_10") (pintype "power_in"))
      (node (ref "PORTA") (pin "35") (pinfunction "35_35") (pintype "passive"))
      (node (ref "PORTA") (pin "36") (pinfunction "36_36") (pintype "passive"))
      (node (ref "PORTA") (pin "37") (pinfunction "37_37") (pintype "passive"))
      (node (ref "PORTA") (pin "38") (pinfunction "38_38") (pintype "passive"))
      (node (ref "PORTB") (pin "35") (pinfunction "35_35") (pintype "passive"))
      (node (ref "PORTB") (pin "36") (pinfunction "36_36") (pintype "passive"))
      (node (ref "PORTB") (pin "37") (pinfunction "37_37") (pintype "passive"))
      (node (ref "PORTB") (pin "38") (pinfunction "38_38") (pintype "passive"))
    )
    (net (code "15") (name "DVDDOUT") (class "Default")
      (node (ref "CD2") (pin "1") (pinfunction "1_1") (pintype "passive"))
      (node (ref "CD3") (pin "1") (pinfunction "1_1") (pintype "passive"))
      (node (ref "ICD1") (pin "3") (pinfunction "DVDDOUT_3") (pintype "output"))
    )
    (net (code "16") (name "GND") (class "Default")
      (node (ref "CP1") (pin "-") (pinfunction "-_-") (pintype "passive"))
      (node (ref "CP2") (pin "-") (pinfunction "-_-") (pintype "passive"))
      (node (ref "CP3") (pin "2") (pinfunction "2_2") (pintype "passive"))
      (node (ref "CP4") (pin "-") (pinfunction "-_-") (pintype "passive"))
      (node (ref "DP1") (pin "A") (pinfunction "A_A") (pintype "passive"))
      (node (ref "FBP3") (pin "1") (pinfunction "P$1_1") (pintype "passive"))
      (node (ref "ICP1") (pin "1") (pinfunction "SHDN_1") (pintype "bidirectional"))
      (node (ref "ICP1") (pin "5") (pinfunction "GND_5") (pintype "power_in"))
      (node (ref "ICP1") (pin "6") (pinfunction "GND_6") (pintype "power_in"))
      (node (ref "ICP1") (pin "7") (pinfunction "GND_7") (pintype "power_in"))
      (node (ref "ICP1") (pin "8") (pinfunction "GND_8") (pintype "power_in"))
      (node (ref "ICP2") (pin "1") (pinfunction "AGND_1") (pintype "power_in"))
      (node (ref "JP1") (pin "2") (pinfunction "2_2") (pintype "passive"))
      (node (ref "JP1") (pin "3") (pinfunction "3_3") (pintype "passive"))
      (node (ref "JP2") (pin "1") (pinfunction "1_1") (pintype "passive"))
      (node (ref "SP1") (pin "3") (pinfunction "3_3") (pintype "passive"))
    )
    (net (code "17") (name "IAN") (class "Default")
      (node (ref "CIA2") (pin "2") (pinfunction "2_2") (pintype "passive"))
      (node (ref "IAN") (pin "TP") (pinfunction "TP_TP") (pintype "input"))
      (node (ref "ICD1") (pin "8") (pinfunction "IAN_8") (pintype "input"))
      (node (ref "RIA4") (pin "2") (pinfunction "2_2") (pintype "passive"))
    )
    (net (code "18") (name "IAP") (class "Default")
      (node (ref "CIA1") (pin "1") (pinfunction "1_1") (pintype "passive"))
      (node (ref "IAP") (pin "TP") (pinfunction "TP_TP") (pintype "input"))
      (node (ref "ICD1") (pin "7") (pinfunction "IAP_7") (pintype "input"))
      (node (ref "RIA3") (pin "2") (pinfunction "2_2") (pintype "passive"))
    )
    (net (code "19") (name "IBN") (class "Default")
      (node (ref "CIB2") (pin "2") (pinfunction "2_2") (pintype "passive"))
      (node (ref "IBN") (pin "TP") (pinfunction "TP_TP") (pintype "input"))
      (node (ref "ICD1") (pin "10") (pinfunction "IBN_10") (pintype "input"))
      (node (ref "RIB4") (pin "2") (pinfunction "2_2") (pintype "passive"))
    )
    (net (code "20") (name "IBP") (class "Default")
      (node (ref "CIB1") (pin "1") (pinfunction "1_1") (pintype "passive"))
      (node (ref "IBP") (pin "TP") (pinfunction "TP_TP") (pintype "input"))
      (node (ref "ICD1") (pin "9") (pinfunction "IBP_9") (pintype "input"))
      (node (ref "RIB3") (pin "2") (pinfunction "2_2") (pintype "passive"))
    )
    (net (code "21") (name "ICN") (class "Default")
      (node (ref "CIC2") (pin "2") (pinfunction "2_2") (pintype "passive"))
      (node (ref "ICD1") (pin "12") (pinfunction "ICN_12") (pintype "input"))
      (node (ref "ICN") (pin "TP") (pinfunction "TP_TP") (pintype "input"))
      (node (ref "RIC4") (pin "2") (pinfunction "2_2") (pintype "passive"))
    )
    (net (code "22") (name "ICP") (class "Default")
      (node (ref "CIC1") (pin "1") (pinfunction "1_1") (pintype "passive"))
      (node (ref "ICD1") (pin "11") (pinfunction "ICP_11") (pintype "input"))
      (node (ref "ICP") (pin "TP") (pinfunction "TP_TP") (pintype "input"))
      (node (ref "RIC3") (pin "2") (pinfunction "2_2") (pintype "passive"))
    )
    (net (code "23") (name "INN") (class "Default")
      (node (ref "CIN2") (pin "2") (pinfunction "2_2") (pintype "passive"))
      (node (ref "ICD1") (pin "14") (pinfunction "INN_14") (pintype "input"))
      (node (ref "INN") (pin "TP") (pinfunction "TP_TP") (pintype "input"))
      (node (ref "RIN4") (pin "2") (pinfunction "2_2") (pintype "passive"))
    )
    (net (code "24") (name "INP") (class "Default")
      (node (ref "CIN1") (pin "1") (pinfunction "1_1") (pintype "passive"))
      (node (ref "ICD1") (pin "13") (pinfunction "INP_13") (pintype "input"))
      (node (ref "INP") (pin "TP") (pinfunction "TP_TP") (pintype "input"))
      (node (ref "RIN3") (pin "2") (pinfunction "2_2") (pintype "passive"))
    )
    (net (code "25") (name "M-DIN") (class "Default")
      (node (ref "MODEM") (pin "3") (pinfunction "DIN_3") (pintype "input"))
    )
    (net (code "26") (name "M-DOUT") (class "Default")
      (node (ref "MODEM") (pin "2") (pinfunction "DOUT_2") (pintype "output"))
    )
    (net (code "27") (name "M-~{CTS}") (class "Default")
      (node (ref "MODEM") (pin "12") (pinfunction "~{CTS}_12") (pintype "bidirectional"))
    )
    (net (code "28") (name "M-~{RTS}") (class "Default")
      (node (ref "MODEM") (pin "16") (pinfunction "~{RTS}_16") (pintype "bidirectional"))
    )
    (net (code "29") (name "MISO") (class "Default")
      (node (ref "ICD1") (pin "38") (pinfunction "MISO_38") (pintype "output"))
    )
    (net (code "30") (name "MOSI") (class "Default")
      (node (ref "ICD1") (pin "39") (pinfunction "MOSI_39") (pintype "input"))
    )
    (net (code "31") (name "Net-(EIA1-P$1)") (class "Default")
      (node (ref "EIA1") (pin "1") (pinfunction "P$1_1") (pintype "passive"))
      (node (ref "IAP_IN") (pin "P1") (pinfunction "P1_P1") (pintype "bidirectional"))
      (node (ref "RIA1") (pin "2") (pinfunction "2_2") (pintype "passive"))
    )
    (net (code "32") (name "Net-(EIA1-P$2)") (class "Default")
      (node (ref "DIA1") (pin "A") (pinfunction "A_A") (pintype "passive"))
      (node (ref "DIA2") (pin "C") (pinfunction "C_C") (pintype "passive"))
      (node (ref "EIA1") (pin "2") (pinfunction "P$2_2") (pintype "passive"))
      (node (ref "RIA3") (pin "1") (pinfunction "1_1") (pintype "passive"))
    )
    (net (code "33") (name "Net-(EIA2-P$1)") (class "Default")
      (node (ref "EIA2") (pin "1") (pinfunction "P$1_1") (pintype "passive"))
      (node (ref "IAN_IN") (pin "P1") (pinfunction "P1_P1") (pintype "bidirectional"))
      (node (ref "RIA2") (pin "1") (pinfunction "1_1") (pintype "passive"))
    )
    (net (code "34") (name "Net-(EIA2-P$2)") (class "Default")
      (node (ref "DIA3") (pin "C") (pinfunction "C_C") (pintype "passive"))
      (node (ref "DIA4") (pin "A") (pinfunction "A_A") (pintype "passive"))
      (node (ref "EIA2") (pin "2") (pinfunction "P$2_2") (pintype "passive"))
      (node (ref "RIA4") (pin "1") (pinfunction "1_1") (pintype "passive"))
    )
    (net (code "35") (name "Net-(EIB1-P$1)") (class "Default")
      (node (ref "EIB1") (pin "1") (pinfunction "P$1_1") (pintype "passive"))
      (node (ref "IBP_IN") (pin "P1") (pinfunction "P1_P1") (pintype "bidirectional"))
      (node (ref "RIB1") (pin "2") (pinfunction "2_2") (pintype "passive"))
    )
    (net (code "36") (name "Net-(EIB1-P$2)") (class "Default")
      (node (ref "DIB1") (pin "A") (pinfunction "A_A") (pintype "passive"))
      (node (ref "DIB2") (pin "C") (pinfunction "C_C") (pintype "passive"))
      (node (ref "EIB1") (pin "2") (pinfunction "P$2_2") (pintype "passive"))
      (node (ref "RIB3") (pin "1") (pinfunction "1_1") (pintype "passive"))
    )
    (net (code "37") (name "Net-(EIB2-P$1)") (class "Default")
      (node (ref "EIB2") (pin "1") (pinfunction "P$1_1") (pintype "passive"))
      (node (ref "IBN_IN") (pin "P1") (pinfunction "P1_P1") (pintype "bidirectional"))
      (node (ref "RIB2") (pin "1") (pinfunction "1_1") (pintype "passive"))
    )
    (net (code "38") (name "Net-(EIB2-P$2)") (class "Default")
      (node (ref "DIB3") (pin "C") (pinfunction "C_C") (pintype "passive"))
      (node (ref "DIB4") (pin "A") (pinfunction "A_A") (pintype "passive"))
      (node (ref "EIB2") (pin "2") (pinfunction "P$2_2") (pintype "passive"))
      (node (ref "RIB4") (pin "1") (pinfunction "1_1") (pintype "passive"))
    )
    (net (code "39") (name "Net-(EIC1-P$1)") (class "Default")
      (node (ref "EIC1") (pin "1") (pinfunction "P$1_1") (pintype "passive"))
      (node (ref "ICP_IN") (pin "P1") (pinfunction "P1_P1") (pintype "bidirectional"))
      (node (ref "RIC1") (pin "2") (pinfunction "2_2") (pintype "passive"))
    )
    (net (code "40") (name "Net-(EIC1-P$2)") (class "Default")
      (node (ref "DIC1") (pin "A") (pinfunction "A_A") (pintype "passive"))
      (node (ref "DIC2") (pin "C") (pinfunction "C_C") (pintype "passive"))
      (node (ref "EIC1") (pin "2") (pinfunction "P$2_2") (pintype "passive"))
      (node (ref "RIC3") (pin "1") (pinfunction "1_1") (pintype "passive"))
    )
    (net (code "41") (name "Net-(EIC2-P$1)") (class "Default")
      (node (ref "EIC2") (pin "1") (pinfunction "P$1_1") (pintype "passive"))
      (node (ref "ICN_IN") (pin "P1") (pinfunction "P1_P1") (pintype "bidirectional"))
      (node (ref "RIC2") (pin "1") (pinfunction "1_1") (pintype "passive"))
    )
    (net (code "42") (name "Net-(EIC2-P$2)") (class "Default")
      (node (ref "DIC3") (pin "C") (pinfunction "C_C") (pintype "passive"))
      (node (ref "DIC4") (pin "A") (pinfunction "A_A") (pintype "passive"))
      (node (ref "EIC2") (pin "2") (pinfunction "P$2_2") (pintype "passive"))
      (node (ref "RIC4") (pin "1") (pinfunction "1_1") (pintype "passive"))
    )
    (net (code "43") (name "Net-(EIN1-P$1)") (class "Default")
      (node (ref "EIN1") (pin "1") (pinfunction "P$1_1") (pintype "passive"))
      (node (ref "INP_IN") (pin "P1") (pinfunction "P1_P1") (pintype "bidirectional"))
      (node (ref "RIN1") (pin "2") (pinfunction "2_2") (pintype "passive"))
    )
    (net (code "44") (name "Net-(EIN1-P$2)") (class "Default")
      (node (ref "DIN1") (pin "A") (pinfunction "A_A") (pintype "passive"))
      (node (ref "DIN2") (pin "C") (pinfunction "C_C") (pintype "passive"))
      (node (ref "EIN1") (pin "2") (pinfunction "P$2_2") (pintype "passive"))
      (node (ref "RIN3") (pin "1") (pinfunction "1_1") (pintype "passive"))
    )
    (net (code "45") (name "Net-(EIN2-P$1)") (class "Default")
      (node (ref "EIN2") (pin "1") (pinfunction "P$1_1") (pintype "passive"))
      (node (ref "INN_IN") (pin "P1") (pinfunction "P1_P1") (pintype "bidirectional"))
      (node (ref "RIN2") (pin "1") (pinfunction "1_1") (pintype "passive"))
    )
    (net (code "46") (name "Net-(EIN2-P$2)") (class "Default")
      (node (ref "DIN3") (pin "C") (pinfunction "C_C") (pintype "passive"))
      (node (ref "DIN4") (pin "A") (pinfunction "A_A") (pintype "passive"))
      (node (ref "EIN2") (pin "2") (pinfunction "P$2_2") (pintype "passive"))
      (node (ref "RIN4") (pin "1") (pinfunction "1_1") (pintype "passive"))
    )
    (net (code "47") (name "Net-(EVA1-P$2)") (class "Default")
      (node (ref "EVA1") (pin "2") (pinfunction "P$2_2") (pintype "passive"))
      (node (ref "RVA1") (pin "1") (pinfunction "1_1") (pintype "passive"))
    )
    (net (code "48") (name "Net-(EVB1-P$2)") (class "Default")
      (node (ref "EVB1") (pin "2") (pinfunction "P$2_2") (pintype "passive"))
      (node (ref "RVB1") (pin "1") (pinfunction "1_1") (pintype "passive"))
    )
    (net (code "49") (name "Net-(EVC1-P$2)") (class "Default")
      (node (ref "EVC1") (pin "2") (pinfunction "P$2_2") (pintype "passive"))
      (node (ref "RVC1") (pin "1") (pinfunction "1_1") (pintype "passive"))
    )
    (net (code "50") (name "Net-(ICP1-IN)") (class "Default")
      (node (ref "CP1") (pin "+") (pinfunction "+_+") (pintype "passive"))
      (node (ref "ICP1") (pin "2") (pinfunction "IN_2") (pintype "bidirectional"))
      (node (ref "SP1") (pin "2") (pinfunction "2_2") (pintype "passive"))
    )
    (net (code "51") (name "Net-(ICP1-SW)") (class "Default")
      (node (ref "DP1") (pin "C") (pinfunction "C_C") (pintype "passive"))
      (node (ref "ICP1") (pin "3") (pinfunction "SW_3") (pintype "output"))
      (node (ref "LP1") (pin "1") (pinfunction "1_1") (pintype "passive"))
    )
    (net (code "52") (name "REF") (class "Default")
      (node (ref "CD6") (pin "1") (pinfunction "1_1") (pintype "passive"))
      (node (ref "CD7") (pin "1") (pinfunction "1_1") (pintype "passive"))
      (node (ref "ICD1") (pin "16") (pinfunction "REF_16") (pintype "passive"))
    )
    (net (code "53") (name "SCLK") (class "Default")
      (node (ref "ICD1") (pin "37") (pinfunction "SCLK_37") (pintype "input"))
    )
    (net (code "54") (name "VAN") (class "Default")
      (node (ref "CVA2") (pin "2") (pinfunction "2_2") (pintype "passive"))
      (node (ref "ICD1") (pin "19") (pinfunction "VAN_19") (pintype "input"))
      (node (ref "RVA3") (pin "1") (pinfunction "1_1") (pintype "passive"))
      (node (ref "VAN") (pin "TP") (pinfunction "TP_TP") (pintype "input"))
    )
    (net (code "55") (name "VAP") (class "Default")
      (node (ref "CVA1") (pin "1") (pinfunction "1_1") (pintype "passive"))
      (node (ref "ICD1") (pin "20") (pinfunction "VAP_20") (pintype "input"))
      (node (ref "RVA1") (pin "2") (pinfunction "2_2") (pintype "passive"))
      (node (ref "RVA2") (pin "2") (pinfunction "2_2") (pintype "passive"))
      (node (ref "VAP") (pin "TP") (pinfunction "TP_TP") (pintype "input"))
    )
    (net (code "56") (name "VAP_IN") (class "Default")
      (node (ref "EVA1") (pin "1") (pinfunction "P$1_1") (pintype "passive"))
      (node (ref "VAP_IN") (pin "P1") (pinfunction "P1_P1") (pintype "bidirectional"))
    )
    (net (code "57") (name "VBN") (class "Default")
      (node (ref "CVB2") (pin "2") (pinfunction "2_2") (pintype "passive"))
      (node (ref "ICD1") (pin "21") (pinfunction "VBN_21") (pintype "input"))
      (node (ref "RVB3") (pin "1") (pinfunction "1_1") (pintype "passive"))
      (node (ref "VBN") (pin "TP") (pinfunction "TP_TP") (pintype "input"))
    )
    (net (code "58") (name "VBP") (class "Default")
      (node (ref "CVB1") (pin "1") (pinfunction "1_1") (pintype "passive"))
      (node (ref "ICD1") (pin "22") (pinfunction "VBP_22") (pintype "input"))
      (node (ref "RVB1") (pin "2") (pinfunction "2_2") (pintype "passive"))
      (node (ref "RVB2") (pin "2") (pinfunction "2_2") (pintype "passive"))
      (node (ref "VBP") (pin "TP") (pinfunction "TP_TP") (pintype "input"))
    )
    (net (code "59") (name "VBP_IN") (class "Default")
      (node (ref "EVB1") (pin "1") (pinfunction "P$1_1") (pintype "passive"))
      (node (ref "VBP_IN") (pin "P1") (pinfunction "P1_P1") (pintype "bidirectional"))
    )
    (net (code "60") (name "VCN") (class "Default")
      (node (ref "CVC2") (pin "2") (pinfunction "2_2") (pintype "passive"))
      (node (ref "ICD1") (pin "23") (pinfunction "VCN_23") (pintype "input"))
      (node (ref "RBC3") (pin "1") (pinfunction "1_1") (pintype "passive"))
      (node (ref "VCN") (pin "TP") (pinfunction "TP_TP") (pintype "input"))
    )
    (net (code "61") (name "VCP") (class "Default")
      (node (ref "CVC1") (pin "1") (pinfunction "1_1") (pintype "passive"))
      (node (ref "ICD1") (pin "24") (pinfunction "VCP_24") (pintype "input"))
      (node (ref "RVC1") (pin "2") (pinfunction "2_2") (pintype "passive"))
      (node (ref "RVC2") (pin "2") (pinfunction "2_2") (pintype "passive"))
      (node (ref "VCP") (pin "TP") (pinfunction "TP_TP") (pintype "input"))
    )
    (net (code "62") (name "VCP_IN") (class "Default")
      (node (ref "EVC1") (pin "1") (pinfunction "P$1_1") (pintype "passive"))
      (node (ref "VCP_IN") (pin "P1") (pinfunction "P1_P1") (pintype "bidirectional"))
    )
    (net (code "63") (name "unconnected-(ICD1-NC1-Pad17)") (class "Default")
      (node (ref "ICD1") (pin "17") (pinfunction "NC1_17") (pintype "no_connect"))
    )
    (net (code "64") (name "unconnected-(ICD1-NC2-Pad18)") (class "Default")
      (node (ref "ICD1") (pin "18") (pinfunction "NC2_18") (pintype "no_connect"))
    )
    (net (code "65") (name "unconnected-(MODEM-AD0-Pad20)") (class "Default")
      (node (ref "MODEM") (pin "20") (pinfunction "AD0_20") (pintype "bidirectional"))
    )
    (net (code "66") (name "unconnected-(MODEM-AD1-Pad19)") (class "Default")
      (node (ref "MODEM") (pin "19") (pinfunction "AD1_19") (pintype "bidirectional"))
    )
    (net (code "67") (name "unconnected-(MODEM-AD2-Pad18)") (class "Default")
      (node (ref "MODEM") (pin "18") (pinfunction "AD2_18") (pintype "bidirectional"))
    )
    (net (code "68") (name "unconnected-(MODEM-AD3-Pad17)") (class "Default")
      (node (ref "MODEM") (pin "17") (pinfunction "AD3_17") (pintype "bidirectional"))
    )
    (net (code "69") (name "unconnected-(MODEM-ASSO-Pad15)") (class "Default")
      (node (ref "MODEM") (pin "15") (pinfunction "ASSO_15") (pintype "bidirectional"))
    )
    (net (code "70") (name "unconnected-(MODEM-DIO4-Pad11)") (class "Default")
      (node (ref "MODEM") (pin "11") (pinfunction "DIO4_11") (pintype "bidirectional"))
    )
    (net (code "71") (name "unconnected-(MODEM-DIO12-Pad4)") (class "Default")
      (node (ref "MODEM") (pin "4") (pinfunction "DIO12_4") (pintype "output"))
    )
    (net (code "72") (name "unconnected-(MODEM-ON-Pad13)") (class "Default")
      (node (ref "MODEM") (pin "13") (pinfunction "ON_13") (pintype "output"))
    )
    (net (code "73") (name "unconnected-(MODEM-PWM0-Pad6)") (class "Default")
      (node (ref "MODEM") (pin "6") (pinfunction "PWM0_6") (pintype "output"))
    )
    (net (code "74") (name "unconnected-(MODEM-PWM1-Pad7)") (class "Default")
      (node (ref "MODEM") (pin "7") (pinfunction "PWM1_7") (pintype "output"))
    )
    (net (code "75") (name "unconnected-(MODEM-RESVED-Pad8)") (class "Default")
      (node (ref "MODEM") (pin "8") (pinfunction "RESVED_8") (pintype "bidirectional"))
    )
    (net (code "76") (name "unconnected-(MODEM-VREF-Pad14)") (class "Default")
      (node (ref "MODEM") (pin "14") (pinfunction "VREF_14") (pintype "bidirectional"))
    )
    (net (code "77") (name "unconnected-(MODEM-~{DTR}-Pad9)") (class "Default")
      (node (ref "MODEM") (pin "9") (pinfunction "~{DTR}_9") (pintype "bidirectional"))
    )
    (net (code "78") (name "unconnected-(MODEM-~{RESET}-Pad5)") (class "Default")
      (node (ref "MODEM") (pin "5") (pinfunction "~{RESET}_5") (pintype "bidirectional"))
    )
    (net (code "79") (name "unconnected-(PORTA-Pad1)") (class "Default")
      (node (ref "PORTA") (pin "1") (pinfunction "1_1") (pintype "passive"))
    )
    (net (code "80") (name "unconnected-(PORTA-Pad2)") (class "Default")
      (node (ref "PORTA") (pin "2") (pinfunction "2_2") (pintype "passive"))
    )
    (net (code "81") (name "unconnected-(PORTA-Pad3)") (class "Default")
      (node (ref "PORTA") (pin "3") (pinfunction "3_3") (pintype "passive"))
    )
    (net (code "82") (name "unconnected-(PORTA-Pad4)") (class "Default")
      (node (ref "PORTA") (pin "4") (pinfunction "4_4") (pintype "passive"))
    )
    (net (code "83") (name "unconnected-(PORTA-Pad5)") (class "Default")
      (node (ref "PORTA") (pin "5") (pinfunction "5_5") (pintype "passive"))
    )
    (net (code "84") (name "unconnected-(PORTA-Pad6)") (class "Default")
      (node (ref "PORTA") (pin "6") (pinfunction "6_6") (pintype "passive"))
    )
    (net (code "85") (name "unconnected-(PORTA-Pad7)") (class "Default")
      (node (ref "PORTA") (pin "7") (pinfunction "7_7") (pintype "passive"))
    )
    (net (code "86") (name "unconnected-(PORTA-Pad8)") (class "Default")
      (node (ref "PORTA") (pin "8") (pinfunction "8_8") (pintype "passive"))
    )
    (net (code "87") (name "unconnected-(PORTA-Pad9)") (class "Default")
      (node (ref "PORTA") (pin "9") (pinfunction "9_9") (pintype "passive"))
    )
    (net (code "88") (name "unconnected-(PORTA-Pad10)") (class "Default")
      (node (ref "PORTA") (pin "10") (pinfunction "10_10") (pintype "passive"))
    )
    (net (code "89") (name "unconnected-(PORTA-Pad11)") (class "Default")
      (node (ref "PORTA") (pin "11") (pinfunction "11_11") (pintype "passive"))
    )
    (net (code "90") (name "unconnected-(PORTA-Pad12)") (class "Default")
      (node (ref "PORTA") (pin "12") (pinfunction "12_12") (pintype "passive"))
    )
    (net (code "91") (name "unconnected-(PORTA-Pad13)") (class "Default")
      (node (ref "PORTA") (pin "13") (pinfunction "13_13") (pintype "passive"))
    )
    (net (code "92") (name "unconnected-(PORTA-Pad14)") (class "Default")
      (node (ref "PORTA") (pin "14") (pinfunction "14_14") (pintype "passive"))
    )
    (net (code "93") (name "unconnected-(PORTA-Pad15)") (class "Default")
      (node (ref "PORTA") (pin "15") (pinfunction "15_15") (pintype "passive"))
    )
    (net (code "94") (name "unconnected-(PORTA-Pad16)") (class "Default")
      (node (ref "PORTA") (pin "16") (pinfunction "16_16") (pintype "passive"))
    )
    (net (code "95") (name "unconnected-(PORTA-Pad17)") (class "Default")
      (node (ref "PORTA") (pin "17") (pinfunction "17_17") (pintype "passive"))
    )
    (net (code "96") (name "unconnected-(PORTA-Pad18)") (class "Default")
      (node (ref "PORTA") (pin "18") (pinfunction "18_18") (pintype "passive"))
    )
    (net (code "97") (name "unconnected-(PORTA-Pad19)") (class "Default")
      (node (ref "PORTA") (pin "19") (pinfunction "19_19") (pintype "passive"))
    )
    (net (code "98") (name "unconnected-(PORTA-Pad20)") (class "Default")
      (node (ref "PORTA") (pin "20") (pinfunction "20_20") (pintype "passive"))
    )
    (net (code "99") (name "unconnected-(PORTA-Pad21)") (class "Default")
      (node (ref "PORTA") (pin "21") (pinfunction "21_21") (pintype "passive"))
    )
    (net (code "100") (name "unconnected-(PORTA-Pad22)") (class "Default")
      (node (ref "PORTA") (pin "22") (pinfunction "22_22") (pintype "passive"))
    )
    (net (code "101") (name "unconnected-(PORTA-Pad23)") (class "Default")
      (node (ref "PORTA") (pin "23") (pinfunction "23_23") (pintype "passive"))
    )
    (net (code "102") (name "unconnected-(PORTA-Pad24)") (class "Default")
      (node (ref "PORTA") (pin "24") (pinfunction "24_24") (pintype "passive"))
    )
    (net (code "103") (name "unconnected-(PORTA-Pad25)") (class "Default")
      (node (ref "PORTA") (pin "25") (pinfunction "25_25") (pintype "passive"))
    )
    (net (code "104") (name "unconnected-(PORTA-Pad26)") (class "Default")
      (node (ref "PORTA") (pin "26") (pinfunction "26_26") (pintype "passive"))
    )
    (net (code "105") (name "unconnected-(PORTA-Pad27)") (class "Default")
      (node (ref "PORTA") (pin "27") (pinfunction "27_27") (pintype "passive"))
    )
    (net (code "106") (name "unconnected-(PORTA-Pad28)") (class "Default")
      (node (ref "PORTA") (pin "28") (pinfunction "28_28") (pintype "passive"))
    )
    (net (code "107") (name "unconnected-(PORTA-Pad29)") (class "Default")
      (node (ref "PORTA") (pin "29") (pinfunction "29_29") (pintype "passive"))
    )
    (net (code "108") (name "unconnected-(PORTA-Pad30)") (class "Default")
      (node (ref "PORTA") (pin "30") (pinfunction "30_30") (pintype "passive"))
    )
    (net (code "109") (name "unconnected-(PORTA-Pad31)") (class "Default")
      (node (ref "PORTA") (pin "31") (pinfunction "31_31") (pintype "passive"))
    )
    (net (code "110") (name "unconnected-(PORTA-Pad32)") (class "Default")
      (node (ref "PORTA") (pin "32") (pinfunction "32_32") (pintype "passive"))
    )
    (net (code "111") (name "unconnected-(PORTA-Pad33)") (class "Default")
      (node (ref "PORTA") (pin "33") (pinfunction "33_33") (pintype "passive"))
    )
    (net (code "112") (name "unconnected-(PORTA-Pad34)") (class "Default")
      (node (ref "PORTA") (pin "34") (pinfunction "34_34") (pintype "passive"))
    )
    (net (code "113") (name "unconnected-(PORTA-Pad39)") (class "Default")
      (node (ref "PORTA") (pin "39") (pinfunction "39_39") (pintype "passive"))
    )
    (net (code "114") (name "unconnected-(PORTA-Pad40)") (class "Default")
      (node (ref "PORTA") (pin "40") (pinfunction "40_40") (pintype "passive"))
    )
    (net (code "115") (name "unconnected-(PORTB-Pad1)") (class "Default")
      (node (ref "PORTB") (pin "1") (pinfunction "1_1") (pintype "passive"))
    )
    (net (code "116") (name "unconnected-(PORTB-Pad2)") (class "Default")
      (node (ref "PORTB") (pin "2") (pinfunction "2_2") (pintype "passive"))
    )
    (net (code "117") (name "unconnected-(PORTB-Pad3)") (class "Default")
      (node (ref "PORTB") (pin "3") (pinfunction "3_3") (pintype "passive"))
    )
    (net (code "118") (name "unconnected-(PORTB-Pad4)") (class "Default")
      (node (ref "PORTB") (pin "4") (pinfunction "4_4") (pintype "passive"))
    )
    (net (code "119") (name "unconnected-(PORTB-Pad5)") (class "Default")
      (node (ref "PORTB") (pin "5") (pinfunction "5_5") (pintype "passive"))
    )
    (net (code "120") (name "unconnected-(PORTB-Pad6)") (class "Default")
      (node (ref "PORTB") (pin "6") (pinfunction "6_6") (pintype "passive"))
    )
    (net (code "121") (name "unconnected-(PORTB-Pad7)") (class "Default")
      (node (ref "PORTB") (pin "7") (pinfunction "7_7") (pintype "passive"))
    )
    (net (code "122") (name "unconnected-(PORTB-Pad8)") (class "Default")
      (node (ref "PORTB") (pin "8") (pinfunction "8_8") (pintype "passive"))
    )
    (net (code "123") (name "unconnected-(PORTB-Pad9)") (class "Default")
      (node (ref "PORTB") (pin "9") (pinfunction "9_9") (pintype "passive"))
    )
    (net (code "124") (name "unconnected-(PORTB-Pad10)") (class "Default")
      (node (ref "PORTB") (pin "10") (pinfunction "10_10") (pintype "passive"))
    )
    (net (code "125") (name "unconnected-(PORTB-Pad11)") (class "Default")
      (node (ref "PORTB") (pin "11") (pinfunction "11_11") (pintype "passive"))
    )
    (net (code "126") (name "unconnected-(PORTB-Pad12)") (class "Default")
      (node (ref "PORTB") (pin "12") (pinfunction "12_12") (pintype "passive"))
    )
    (net (code "127") (name "unconnected-(PORTB-Pad13)") (class "Default")
      (node (ref "PORTB") (pin "13") (pinfunction "13_13") (pintype "passive"))
    )
    (net (code "128") (name "unconnected-(PORTB-Pad14)") (class "Default")
      (node (ref "PORTB") (pin "14") (pinfunction "14_14") (pintype "passive"))
    )
    (net (code "129") (name "unconnected-(PORTB-Pad15)") (class "Default")
      (node (ref "PORTB") (pin "15") (pinfunction "15_15") (pintype "passive"))
    )
    (net (code "130") (name "unconnected-(PORTB-Pad16)") (class "Default")
      (node (ref "PORTB") (pin "16") (pinfunction "16_16") (pintype "passive"))
    )
    (net (code "131") (name "unconnected-(PORTB-Pad17)") (class "Default")
      (node (ref "PORTB") (pin "17") (pinfunction "17_17") (pintype "passive"))
    )
    (net (code "132") (name "unconnected-(PORTB-Pad18)") (class "Default")
      (node (ref "PORTB") (pin "18") (pinfunction "18_18") (pintype "passive"))
    )
    (net (code "133") (name "unconnected-(PORTB-Pad19)") (class "Default")
      (node (ref "PORTB") (pin "19") (pinfunction "19_19") (pintype "passive"))
    )
    (net (code "134") (name "unconnected-(PORTB-Pad20)") (class "Default")
      (node (ref "PORTB") (pin "20") (pinfunction "20_20") (pintype "passive"))
    )
    (net (code "135") (name "unconnected-(PORTB-Pad21)") (class "Default")
      (node (ref "PORTB") (pin "21") (pinfunction "21_21") (pintype "passive"))
    )
    (net (code "136") (name "unconnected-(PORTB-Pad22)") (class "Default")
      (node (ref "PORTB") (pin "22") (pinfunction "22_22") (pintype "passive"))
    )
    (net (code "137") (name "unconnected-(PORTB-Pad23)") (class "Default")
      (node (ref "PORTB") (pin "23") (pinfunction "23_23") (pintype "passive"))
    )
    (net (code "138") (name "unconnected-(PORTB-Pad24)") (class "Default")
      (node (ref "PORTB") (pin "24") (pinfunction "24_24") (pintype "passive"))
    )
    (net (code "139") (name "unconnected-(PORTB-Pad25)") (class "Default")
      (node (ref "PORTB") (pin "25") (pinfunction "25_25") (pintype "passive"))
    )
    (net (code "140") (name "unconnected-(PORTB-Pad26)") (class "Default")
      (node (ref "PORTB") (pin "26") (pinfunction "26_26") (pintype "passive"))
    )
    (net (code "141") (name "unconnected-(PORTB-Pad27)") (class "Default")
      (node (ref "PORTB") (pin "27") (pinfunction "27_27") (pintype "passive"))
    )
    (net (code "142") (name "unconnected-(PORTB-Pad28)") (class "Default")
      (node (ref "PORTB") (pin "28") (pinfunction "28_28") (pintype "passive"))
    )
    (net (code "143") (name "unconnected-(PORTB-Pad29)") (class "Default")
      (node (ref "PORTB") (pin "29") (pinfunction "29_29") (pintype "passive"))
    )
    (net (code "144") (name "unconnected-(PORTB-Pad30)") (class "Default")
      (node (ref "PORTB") (pin "30") (pinfunction "30_30") (pintype "passive"))
    )
    (net (code "145") (name "unconnected-(PORTB-Pad31)") (class "Default")
      (node (ref "PORTB") (pin "31") (pinfunction "31_31") (pintype "passive"))
    )
    (net (code "146") (name "unconnected-(PORTB-Pad32)") (class "Default")
      (node (ref "PORTB") (pin "32") (pinfunction "32_32") (pintype "passive"))
    )
    (net (code "147") (name "unconnected-(PORTB-Pad33)") (class "Default")
      (node (ref "PORTB") (pin "33") (pinfunction "33_33") (pintype "passive"))
    )
    (net (code "148") (name "unconnected-(PORTB-Pad34)") (class "Default")
      (node (ref "PORTB") (pin "34") (pinfunction "34_34") (pintype "passive"))
    )
    (net (code "149") (name "unconnected-(PORTB-Pad39)") (class "Default")
      (node (ref "PORTB") (pin "39") (pinfunction "39_39") (pintype "passive"))
    )
    (net (code "150") (name "unconnected-(PORTB-Pad40)") (class "Default")
      (node (ref "PORTB") (pin "40") (pinfunction "40_40") (pintype "passive"))
    )
    (net (code "151") (name "~{IRQ0}") (class "Default")
      (node (ref "ICD1") (pin "31") (pinfunction "~{IRQ0}_31") (pintype "output"))
    )
    (net (code "152") (name "~{IRQ1}") (class "Default")
      (node (ref "ICD1") (pin "32") (pinfunction "~{IRQ1}_32") (pintype "output"))
    )
    (net (code "153") (name "~{RESET}") (class "Default")
      (node (ref "CD1") (pin "2") (pinfunction "2_2") (pintype "passive"))
      (node (ref "ICD1") (pin "6") (pinfunction "~{RESET}_6") (pintype "input"))
      (node (ref "RD1") (pin "1") (pinfunction "1_1") (pintype "passive"))
    )
    (net (code "154") (name "~{SS}") (class "Default")
      (node (ref "ICD1") (pin "40") (pinfunction "~{SS}_40") (pintype "input"))
    )
  )
)
